# design.net
KiCad netlist of a schematic drawn in Altium Designer
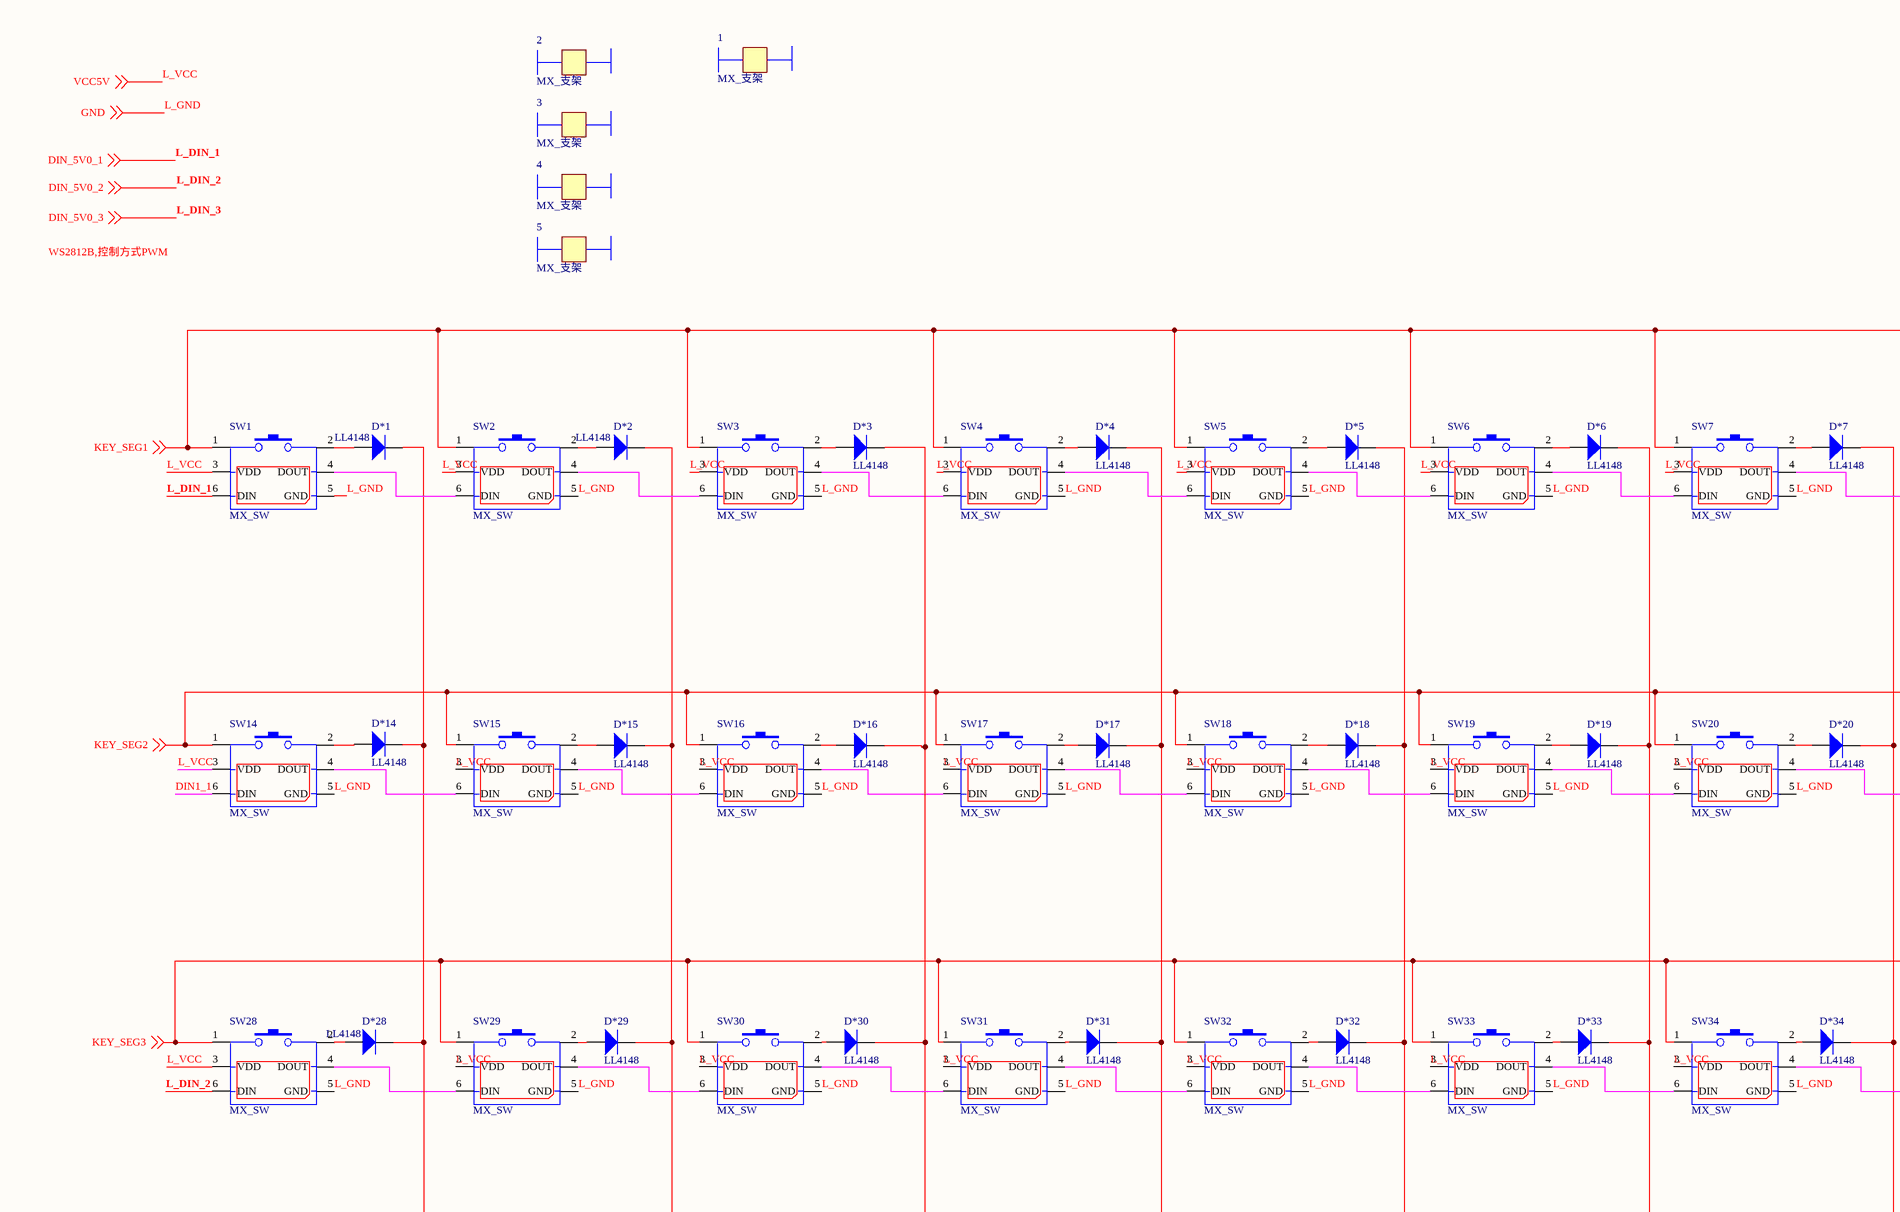
[diagram p0: 机械键盘.SchDoc, top left]
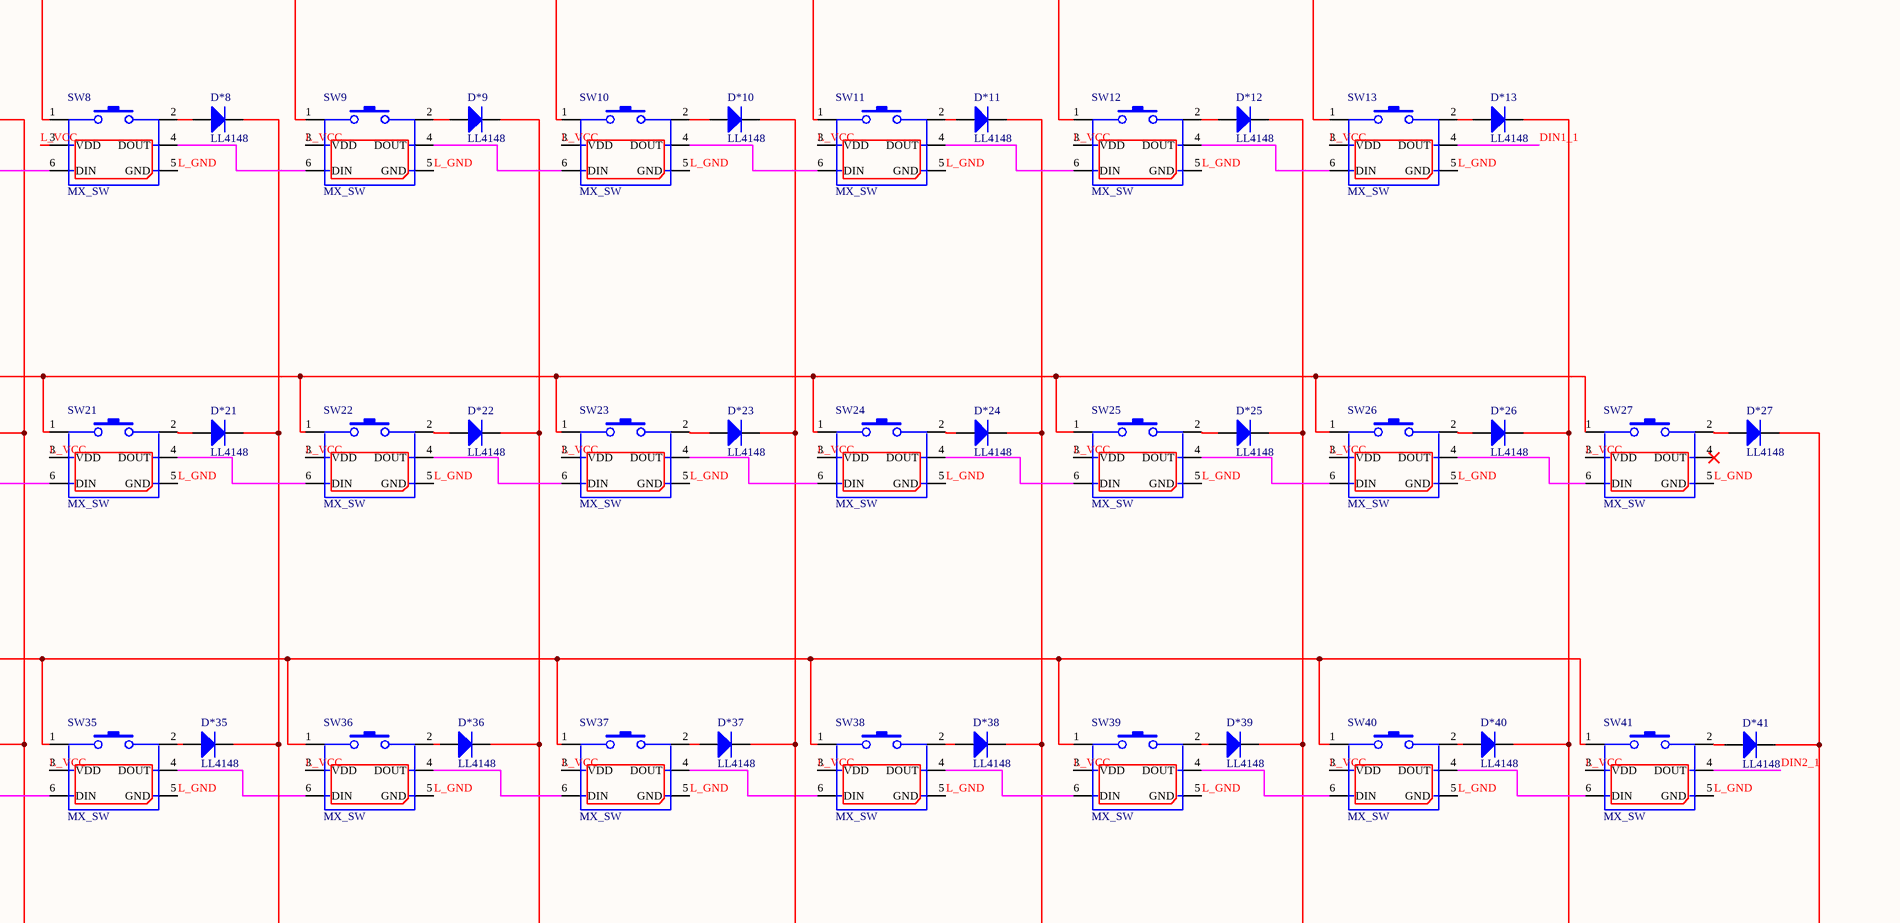
[diagram p1: 机械键盘.SchDoc, top right]
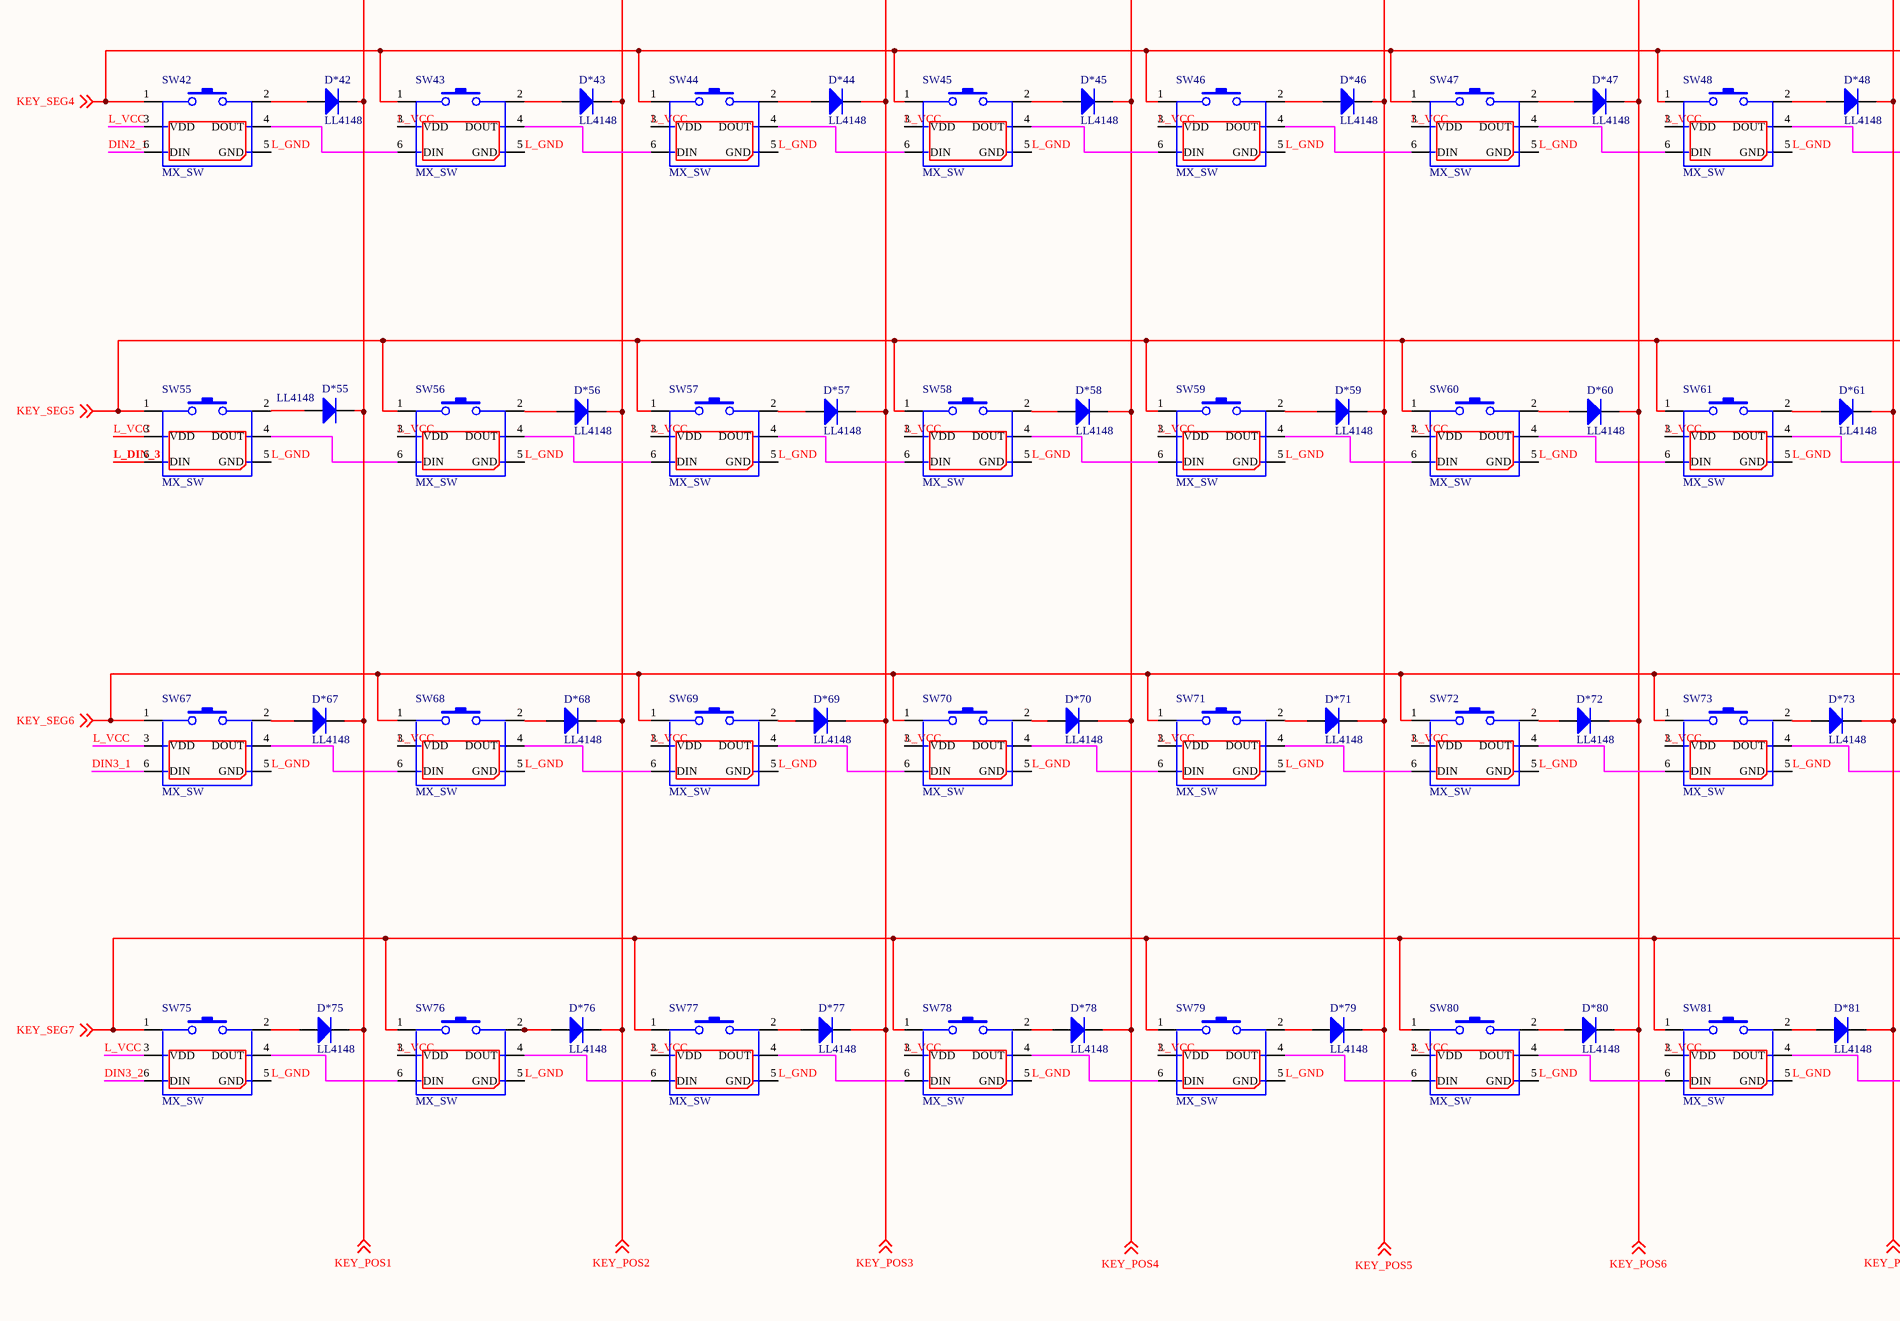
[diagram p2: 机械键盘.SchDoc, bottom left]
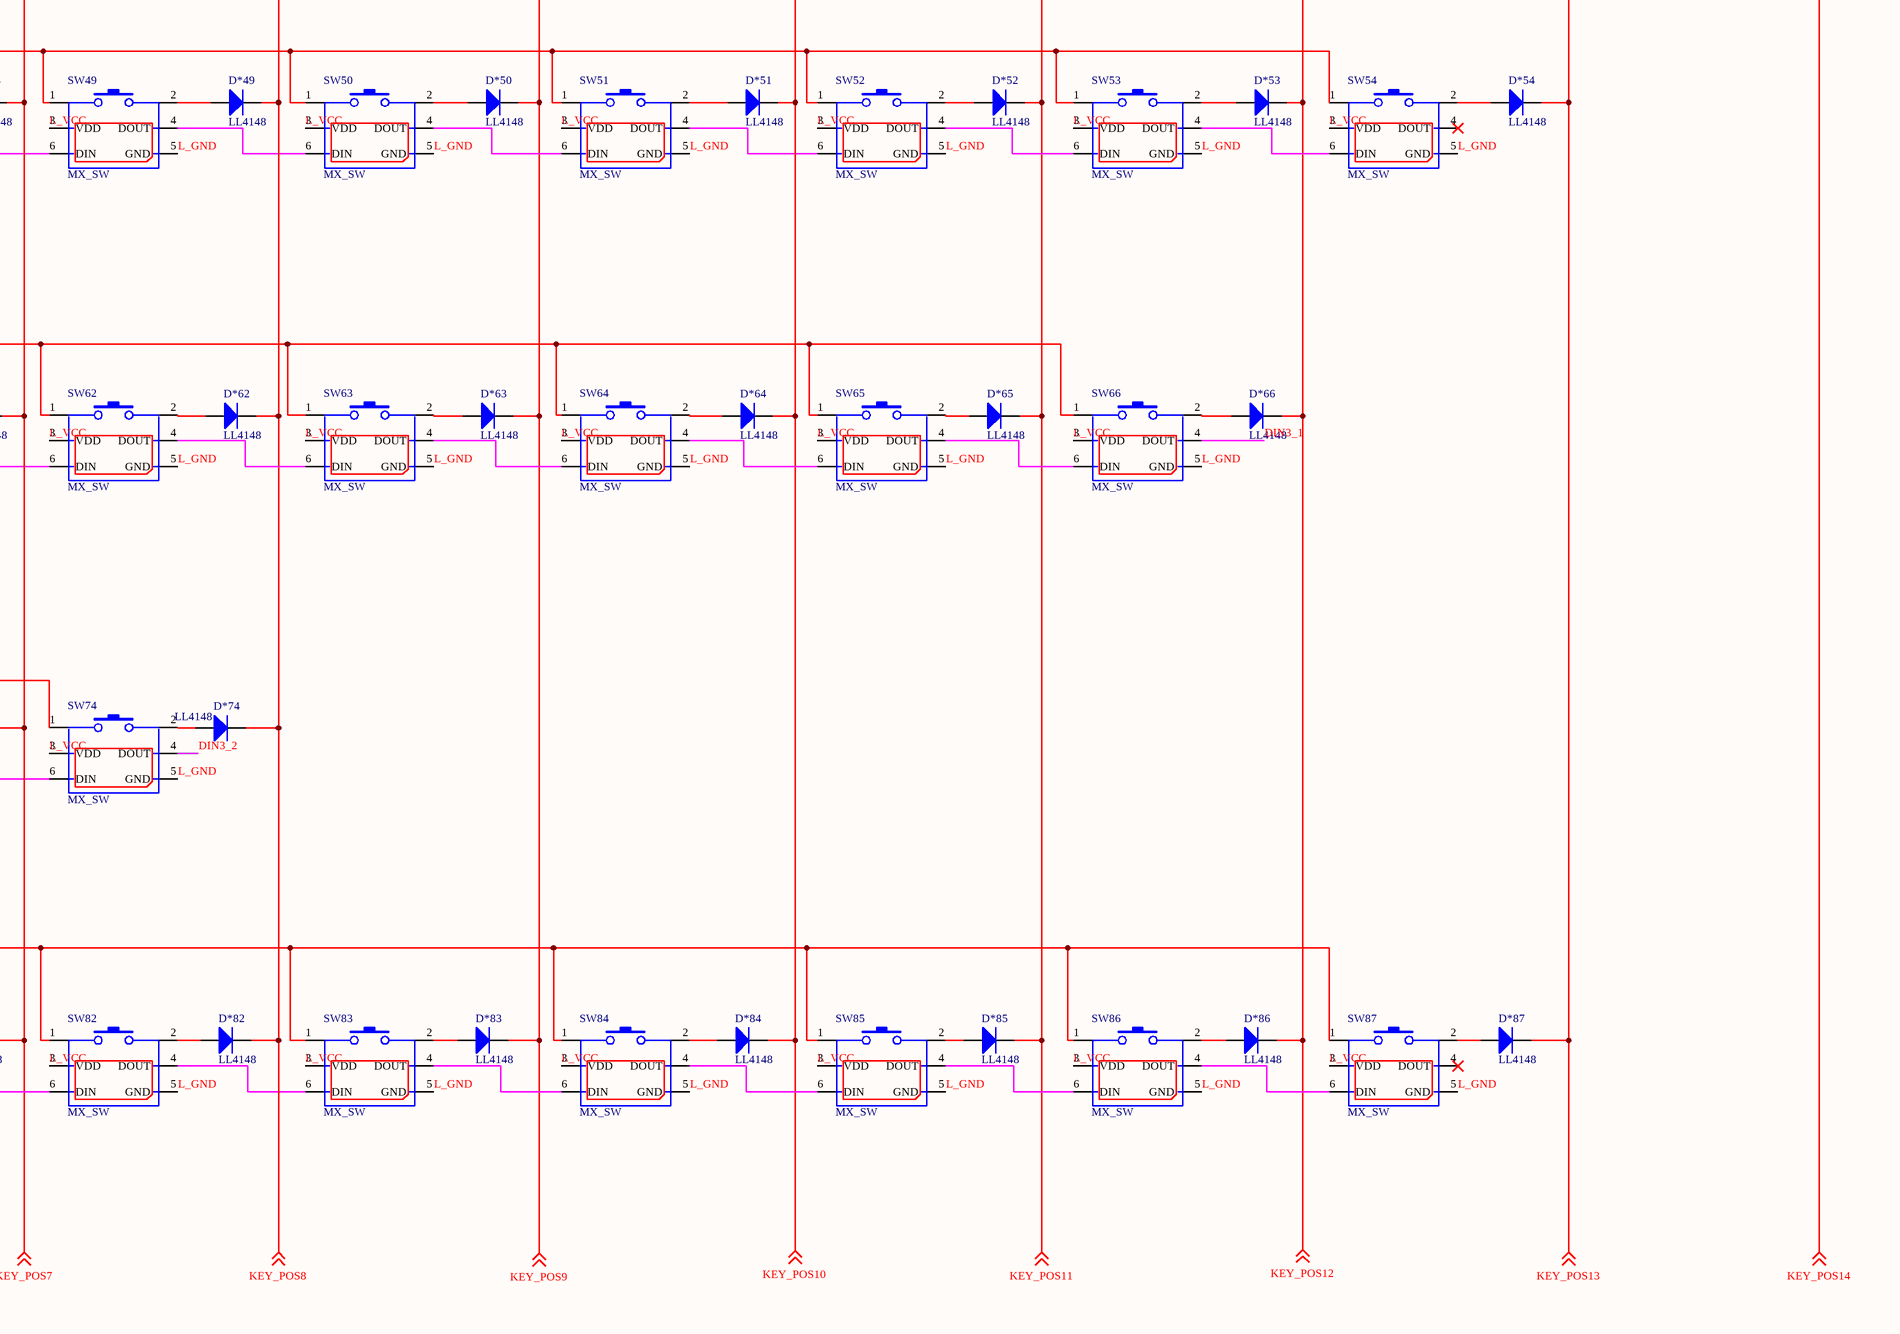
[diagram p3: 机械键盘.SchDoc, bottom right]

(export (version "E")
  (design (tool "Eeschema 10.0.6"))
  (components
    (comp (ref "1") (value "MX_支架") (footprint "机械键盘:1x6.25") (libsource (lib "机械键盘") (part "MX_支架")))
    (comp (ref "2") (value "MX_支架") (footprint "机械键盘:1x2") (libsource (lib "机械键盘") (part "MX_支架")))
    (comp (ref "3") (value "MX_支架") (footprint "机械键盘:1x2") (libsource (lib "机械键盘") (part "MX_支架")))
    (comp (ref "4") (value "MX_支架") (footprint "机械键盘:1x2") (libsource (lib "机械键盘") (part "MX_支架")))
    (comp (ref "5") (value "MX_支架") (footprint "机械键盘:1x2") (libsource (lib "机械键盘") (part "MX_支架")))
    (comp (ref "D*1")
      (value "LL4148")
      (footprint "mx_pcb_library:LL-34_L3.7-W1.6-RD")
      (libsource (lib "mx_pcb_library") (part "LL4148"))
    )
    (comp (ref "D*2")
      (value "LL4148")
      (footprint "mx_pcb_library:LL-34_L3.7-W1.6-RD")
      (libsource (lib "mx_pcb_library") (part "LL4148"))
    )
    (comp (ref "D*3")
      (value "LL4148")
      (footprint "mx_pcb_library:LL-34_L3.7-W1.6-RD")
      (libsource (lib "mx_pcb_library") (part "LL4148"))
    )
    (comp (ref "D*4")
      (value "LL4148")
      (footprint "mx_pcb_library:LL-34_L3.7-W1.6-RD")
      (libsource (lib "mx_pcb_library") (part "LL4148"))
    )
    (comp (ref "D*5")
      (value "LL4148")
      (footprint "mx_pcb_library:LL-34_L3.7-W1.6-RD")
      (libsource (lib "mx_pcb_library") (part "LL4148"))
    )
    (comp (ref "D*6")
      (value "LL4148")
      (footprint "mx_pcb_library:LL-34_L3.7-W1.6-RD")
      (libsource (lib "mx_pcb_library") (part "LL4148"))
    )
    (comp (ref "D*7")
      (value "LL4148")
      (footprint "mx_pcb_library:LL-34_L3.7-W1.6-RD")
      (libsource (lib "mx_pcb_library") (part "LL4148"))
    )
    (comp (ref "D*8")
      (value "LL4148")
      (footprint "mx_pcb_library:LL-34_L3.7-W1.6-RD")
      (libsource (lib "mx_pcb_library") (part "LL4148"))
    )
    (comp (ref "D*9")
      (value "LL4148")
      (footprint "mx_pcb_library:LL-34_L3.7-W1.6-RD")
      (libsource (lib "mx_pcb_library") (part "LL4148"))
    )
    (comp (ref "D*10")
      (value "LL4148")
      (footprint "mx_pcb_library:LL-34_L3.7-W1.6-RD")
      (libsource (lib "mx_pcb_library") (part "LL4148"))
    )
    (comp (ref "D*11")
      (value "LL4148")
      (footprint "mx_pcb_library:LL-34_L3.7-W1.6-RD")
      (libsource (lib "mx_pcb_library") (part "LL4148"))
    )
    (comp (ref "D*12")
      (value "LL4148")
      (footprint "mx_pcb_library:LL-34_L3.7-W1.6-RD")
      (libsource (lib "mx_pcb_library") (part "LL4148"))
    )
    (comp (ref "D*13")
      (value "LL4148")
      (footprint "mx_pcb_library:LL-34_L3.7-W1.6-RD")
      (libsource (lib "mx_pcb_library") (part "LL4148"))
    )
    (comp (ref "D*14")
      (value "LL4148")
      (footprint "mx_pcb_library:LL-34_L3.7-W1.6-RD")
      (libsource (lib "mx_pcb_library") (part "LL4148"))
    )
    (comp (ref "D*15")
      (value "LL4148")
      (footprint "mx_pcb_library:LL-34_L3.7-W1.6-RD")
      (libsource (lib "mx_pcb_library") (part "LL4148"))
    )
    (comp (ref "D*16")
      (value "LL4148")
      (footprint "mx_pcb_library:LL-34_L3.7-W1.6-RD")
      (libsource (lib "mx_pcb_library") (part "LL4148"))
    )
    (comp (ref "D*17")
      (value "LL4148")
      (footprint "mx_pcb_library:LL-34_L3.7-W1.6-RD")
      (libsource (lib "mx_pcb_library") (part "LL4148"))
    )
    (comp (ref "D*18")
      (value "LL4148")
      (footprint "mx_pcb_library:LL-34_L3.7-W1.6-RD")
      (libsource (lib "mx_pcb_library") (part "LL4148"))
    )
    (comp (ref "D*19")
      (value "LL4148")
      (footprint "mx_pcb_library:LL-34_L3.7-W1.6-RD")
      (libsource (lib "mx_pcb_library") (part "LL4148"))
    )
    (comp (ref "D*20")
      (value "LL4148")
      (footprint "mx_pcb_library:LL-34_L3.7-W1.6-RD")
      (libsource (lib "mx_pcb_library") (part "LL4148"))
    )
    (comp (ref "D*21")
      (value "LL4148")
      (footprint "mx_pcb_library:LL-34_L3.7-W1.6-RD")
      (libsource (lib "mx_pcb_library") (part "LL4148"))
    )
    (comp (ref "D*22")
      (value "LL4148")
      (footprint "mx_pcb_library:LL-34_L3.7-W1.6-RD")
      (libsource (lib "mx_pcb_library") (part "LL4148"))
    )
    (comp (ref "D*23")
      (value "LL4148")
      (footprint "mx_pcb_library:LL-34_L3.7-W1.6-RD")
      (libsource (lib "mx_pcb_library") (part "LL4148"))
    )
    (comp (ref "D*24")
      (value "LL4148")
      (footprint "mx_pcb_library:LL-34_L3.7-W1.6-RD")
      (libsource (lib "mx_pcb_library") (part "LL4148"))
    )
    (comp (ref "D*25")
      (value "LL4148")
      (footprint "mx_pcb_library:LL-34_L3.7-W1.6-RD")
      (libsource (lib "mx_pcb_library") (part "LL4148"))
    )
    (comp (ref "D*26")
      (value "LL4148")
      (footprint "mx_pcb_library:LL-34_L3.7-W1.6-RD")
      (libsource (lib "mx_pcb_library") (part "LL4148"))
    )
    (comp (ref "D*27")
      (value "LL4148")
      (footprint "mx_pcb_library:LL-34_L3.7-W1.6-RD")
      (libsource (lib "mx_pcb_library") (part "LL4148"))
    )
    (comp (ref "D*28")
      (value "LL4148")
      (footprint "mx_pcb_library:LL-34_L3.7-W1.6-RD")
      (libsource (lib "mx_pcb_library") (part "LL4148"))
    )
    (comp (ref "D*29")
      (value "LL4148")
      (footprint "mx_pcb_library:LL-34_L3.7-W1.6-RD")
      (libsource (lib "mx_pcb_library") (part "LL4148"))
    )
    (comp (ref "D*30")
      (value "LL4148")
      (footprint "mx_pcb_library:LL-34_L3.7-W1.6-RD")
      (libsource (lib "mx_pcb_library") (part "LL4148"))
    )
    (comp (ref "D*31")
      (value "LL4148")
      (footprint "mx_pcb_library:LL-34_L3.7-W1.6-RD")
      (libsource (lib "mx_pcb_library") (part "LL4148"))
    )
    (comp (ref "D*32")
      (value "LL4148")
      (footprint "mx_pcb_library:LL-34_L3.7-W1.6-RD")
      (libsource (lib "mx_pcb_library") (part "LL4148"))
    )
    (comp (ref "D*33")
      (value "LL4148")
      (footprint "mx_pcb_library:LL-34_L3.7-W1.6-RD")
      (libsource (lib "mx_pcb_library") (part "LL4148"))
    )
    (comp (ref "D*34")
      (value "LL4148")
      (footprint "mx_pcb_library:LL-34_L3.7-W1.6-RD")
      (libsource (lib "mx_pcb_library") (part "LL4148"))
    )
    (comp (ref "D*35")
      (value "LL4148")
      (footprint "mx_pcb_library:LL-34_L3.7-W1.6-RD")
      (libsource (lib "mx_pcb_library") (part "LL4148"))
    )
    (comp (ref "D*36")
      (value "LL4148")
      (footprint "mx_pcb_library:LL-34_L3.7-W1.6-RD")
      (libsource (lib "mx_pcb_library") (part "LL4148"))
    )
    (comp (ref "D*37")
      (value "LL4148")
      (footprint "mx_pcb_library:LL-34_L3.7-W1.6-RD")
      (libsource (lib "mx_pcb_library") (part "LL4148"))
    )
    (comp (ref "D*38")
      (value "LL4148")
      (footprint "mx_pcb_library:LL-34_L3.7-W1.6-RD")
      (libsource (lib "mx_pcb_library") (part "LL4148"))
    )
    (comp (ref "D*39")
      (value "LL4148")
      (footprint "mx_pcb_library:LL-34_L3.7-W1.6-RD")
      (libsource (lib "mx_pcb_library") (part "LL4148"))
    )
    (comp (ref "D*40")
      (value "LL4148")
      (footprint "mx_pcb_library:LL-34_L3.7-W1.6-RD")
      (libsource (lib "mx_pcb_library") (part "LL4148"))
    )
    (comp (ref "D*41")
      (value "LL4148")
      (footprint "mx_pcb_library:LL-34_L3.7-W1.6-RD")
      (libsource (lib "mx_pcb_library") (part "LL4148"))
    )
    (comp (ref "D*42")
      (value "LL4148")
      (footprint "mx_pcb_library:LL-34_L3.7-W1.6-RD")
      (libsource (lib "mx_pcb_library") (part "LL4148"))
    )
    (comp (ref "D*43")
      (value "LL4148")
      (footprint "mx_pcb_library:LL-34_L3.7-W1.6-RD")
      (libsource (lib "mx_pcb_library") (part "LL4148"))
    )
    (comp (ref "D*44")
      (value "LL4148")
      (footprint "mx_pcb_library:LL-34_L3.7-W1.6-RD")
      (libsource (lib "mx_pcb_library") (part "LL4148"))
    )
    (comp (ref "D*45")
      (value "LL4148")
      (footprint "mx_pcb_library:LL-34_L3.7-W1.6-RD")
      (libsource (lib "mx_pcb_library") (part "LL4148"))
    )
    (comp (ref "D*46")
      (value "LL4148")
      (footprint "mx_pcb_library:LL-34_L3.7-W1.6-RD")
      (libsource (lib "mx_pcb_library") (part "LL4148"))
    )
    (comp (ref "D*47")
      (value "LL4148")
      (footprint "mx_pcb_library:LL-34_L3.7-W1.6-RD")
      (libsource (lib "mx_pcb_library") (part "LL4148"))
    )
    (comp (ref "D*48")
      (value "LL4148")
      (footprint "mx_pcb_library:LL-34_L3.7-W1.6-RD")
      (libsource (lib "mx_pcb_library") (part "LL4148"))
    )
    (comp (ref "D*49")
      (value "LL4148")
      (footprint "mx_pcb_library:LL-34_L3.7-W1.6-RD")
      (libsource (lib "mx_pcb_library") (part "LL4148"))
    )
    (comp (ref "D*50")
      (value "LL4148")
      (footprint "mx_pcb_library:LL-34_L3.7-W1.6-RD")
      (libsource (lib "mx_pcb_library") (part "LL4148"))
    )
    (comp (ref "D*51")
      (value "LL4148")
      (footprint "mx_pcb_library:LL-34_L3.7-W1.6-RD")
      (libsource (lib "mx_pcb_library") (part "LL4148"))
    )
    (comp (ref "D*52")
      (value "LL4148")
      (footprint "mx_pcb_library:LL-34_L3.7-W1.6-RD")
      (libsource (lib "mx_pcb_library") (part "LL4148"))
    )
    (comp (ref "D*53")
      (value "LL4148")
      (footprint "mx_pcb_library:LL-34_L3.7-W1.6-RD")
      (libsource (lib "mx_pcb_library") (part "LL4148"))
    )
    (comp (ref "D*54")
      (value "LL4148")
      (footprint "mx_pcb_library:LL-34_L3.7-W1.6-RD")
      (libsource (lib "mx_pcb_library") (part "LL4148"))
    )
    (comp (ref "D*55")
      (value "LL4148")
      (footprint "mx_pcb_library:LL-34_L3.7-W1.6-RD")
      (libsource (lib "mx_pcb_library") (part "LL4148"))
    )
    (comp (ref "D*56")
      (value "LL4148")
      (footprint "mx_pcb_library:LL-34_L3.7-W1.6-RD")
      (libsource (lib "mx_pcb_library") (part "LL4148"))
    )
    (comp (ref "D*57")
      (value "LL4148")
      (footprint "mx_pcb_library:LL-34_L3.7-W1.6-RD")
      (libsource (lib "mx_pcb_library") (part "LL4148"))
    )
    (comp (ref "D*58")
      (value "LL4148")
      (footprint "mx_pcb_library:LL-34_L3.7-W1.6-RD")
      (libsource (lib "mx_pcb_library") (part "LL4148"))
    )
    (comp (ref "D*59")
      (value "LL4148")
      (footprint "mx_pcb_library:LL-34_L3.7-W1.6-RD")
      (libsource (lib "mx_pcb_library") (part "LL4148"))
    )
    (comp (ref "D*60")
      (value "LL4148")
      (footprint "mx_pcb_library:LL-34_L3.7-W1.6-RD")
      (libsource (lib "mx_pcb_library") (part "LL4148"))
    )
    (comp (ref "D*61")
      (value "LL4148")
      (footprint "mx_pcb_library:LL-34_L3.7-W1.6-RD")
      (libsource (lib "mx_pcb_library") (part "LL4148"))
    )
    (comp (ref "D*62")
      (value "LL4148")
      (footprint "mx_pcb_library:LL-34_L3.7-W1.6-RD")
      (libsource (lib "mx_pcb_library") (part "LL4148"))
    )
    (comp (ref "D*63")
      (value "LL4148")
      (footprint "mx_pcb_library:LL-34_L3.7-W1.6-RD")
      (libsource (lib "mx_pcb_library") (part "LL4148"))
    )
    (comp (ref "D*64")
      (value "LL4148")
      (footprint "mx_pcb_library:LL-34_L3.7-W1.6-RD")
      (libsource (lib "mx_pcb_library") (part "LL4148"))
    )
    (comp (ref "D*65")
      (value "LL4148")
      (footprint "mx_pcb_library:LL-34_L3.7-W1.6-RD")
      (libsource (lib "mx_pcb_library") (part "LL4148"))
    )
    (comp (ref "D*66")
      (value "LL4148")
      (footprint "mx_pcb_library:LL-34_L3.7-W1.6-RD")
      (libsource (lib "mx_pcb_library") (part "LL4148"))
    )
    (comp (ref "D*67")
      (value "LL4148")
      (footprint "mx_pcb_library:LL-34_L3.7-W1.6-RD")
      (libsource (lib "mx_pcb_library") (part "LL4148"))
    )
    (comp (ref "D*68")
      (value "LL4148")
      (footprint "mx_pcb_library:LL-34_L3.7-W1.6-RD")
      (libsource (lib "mx_pcb_library") (part "LL4148"))
    )
    (comp (ref "D*69")
      (value "LL4148")
      (footprint "mx_pcb_library:LL-34_L3.7-W1.6-RD")
      (libsource (lib "mx_pcb_library") (part "LL4148"))
    )
    (comp (ref "D*70")
      (value "LL4148")
      (footprint "mx_pcb_library:LL-34_L3.7-W1.6-RD")
      (libsource (lib "mx_pcb_library") (part "LL4148"))
    )
    (comp (ref "D*71")
      (value "LL4148")
      (footprint "mx_pcb_library:LL-34_L3.7-W1.6-RD")
      (libsource (lib "mx_pcb_library") (part "LL4148"))
    )
    (comp (ref "D*72")
      (value "LL4148")
      (footprint "mx_pcb_library:LL-34_L3.7-W1.6-RD")
      (libsource (lib "mx_pcb_library") (part "LL4148"))
    )
    (comp (ref "D*73")
      (value "LL4148")
      (footprint "mx_pcb_library:LL-34_L3.7-W1.6-RD")
      (libsource (lib "mx_pcb_library") (part "LL4148"))
    )
    (comp (ref "D*74")
      (value "LL4148")
      (footprint "mx_pcb_library:LL-34_L3.7-W1.6-RD")
      (libsource (lib "mx_pcb_library") (part "LL4148"))
    )
    (comp (ref "D*75")
      (value "LL4148")
      (footprint "mx_pcb_library:LL-34_L3.7-W1.6-RD")
      (libsource (lib "mx_pcb_library") (part "LL4148"))
    )
    (comp (ref "D*76")
      (value "LL4148")
      (footprint "mx_pcb_library:LL-34_L3.7-W1.6-RD")
      (libsource (lib "mx_pcb_library") (part "LL4148"))
    )
    (comp (ref "D*77")
      (value "LL4148")
      (footprint "mx_pcb_library:LL-34_L3.7-W1.6-RD")
      (libsource (lib "mx_pcb_library") (part "LL4148"))
    )
    (comp (ref "D*78")
      (value "LL4148")
      (footprint "mx_pcb_library:LL-34_L3.7-W1.6-RD")
      (libsource (lib "mx_pcb_library") (part "LL4148"))
    )
    (comp (ref "D*79")
      (value "LL4148")
      (footprint "mx_pcb_library:LL-34_L3.7-W1.6-RD")
      (libsource (lib "mx_pcb_library") (part "LL4148"))
    )
    (comp (ref "D*80")
      (value "LL4148")
      (footprint "mx_pcb_library:LL-34_L3.7-W1.6-RD")
      (libsource (lib "mx_pcb_library") (part "LL4148"))
    )
    (comp (ref "D*81")
      (value "LL4148")
      (footprint "mx_pcb_library:LL-34_L3.7-W1.6-RD")
      (libsource (lib "mx_pcb_library") (part "LL4148"))
    )
    (comp (ref "D*82")
      (value "LL4148")
      (footprint "mx_pcb_library:LL-34_L3.7-W1.6-RD")
      (libsource (lib "mx_pcb_library") (part "LL4148"))
    )
    (comp (ref "D*83")
      (value "LL4148")
      (footprint "mx_pcb_library:LL-34_L3.7-W1.6-RD")
      (libsource (lib "mx_pcb_library") (part "LL4148"))
    )
    (comp (ref "D*84")
      (value "LL4148")
      (footprint "mx_pcb_library:LL-34_L3.7-W1.6-RD")
      (libsource (lib "mx_pcb_library") (part "LL4148"))
    )
    (comp (ref "D*85")
      (value "LL4148")
      (footprint "mx_pcb_library:LL-34_L3.7-W1.6-RD")
      (libsource (lib "mx_pcb_library") (part "LL4148"))
    )
    (comp (ref "D*86")
      (value "LL4148")
      (footprint "mx_pcb_library:LL-34_L3.7-W1.6-RD")
      (libsource (lib "mx_pcb_library") (part "LL4148"))
    )
    (comp (ref "D*87")
      (value "LL4148")
      (footprint "mx_pcb_library:LL-34_L3.7-W1.6-RD")
      (libsource (lib "mx_pcb_library") (part "LL4148"))
    )
    (comp (ref "SW1")
      (value "MX_SW")
      (footprint "机械键盘:MX_SW-7")
      (description "with Fixation pins  1-Pole w/Diode")
      (libsource (lib "机械键盘") (part "MX_SW-7"))
    )
    (comp (ref "SW2")
      (value "MX_SW")
      (footprint "机械键盘:MX_SW-7")
      (description "with Fixation pins  1-Pole w/Diode")
      (libsource (lib "机械键盘") (part "MX_SW-7"))
    )
    (comp (ref "SW3")
      (value "MX_SW")
      (footprint "机械键盘:MX_SW-7")
      (description "with Fixation pins  1-Pole w/Diode")
      (libsource (lib "机械键盘") (part "MX_SW-7"))
    )
    (comp (ref "SW4")
      (value "MX_SW")
      (footprint "机械键盘:MX_SW-7")
      (description "with Fixation pins  1-Pole w/Diode")
      (libsource (lib "机械键盘") (part "MX_SW-7"))
    )
    (comp (ref "SW5")
      (value "MX_SW")
      (footprint "机械键盘:MX_SW-7")
      (description "with Fixation pins  1-Pole w/Diode")
      (libsource (lib "机械键盘") (part "MX_SW-7"))
    )
    (comp (ref "SW6")
      (value "MX_SW")
      (footprint "机械键盘:MX_SW-7")
      (description "with Fixation pins  1-Pole w/Diode")
      (libsource (lib "机械键盘") (part "MX_SW-7"))
    )
    (comp (ref "SW7")
      (value "MX_SW")
      (footprint "机械键盘:MX_SW-7")
      (description "with Fixation pins  1-Pole w/Diode")
      (libsource (lib "机械键盘") (part "MX_SW-7"))
    )
    (comp (ref "SW8")
      (value "MX_SW")
      (footprint "机械键盘:MX_SW-7")
      (description "with Fixation pins  1-Pole w/Diode")
      (libsource (lib "机械键盘") (part "MX_SW-7"))
    )
    (comp (ref "SW9")
      (value "MX_SW")
      (footprint "机械键盘:MX_SW-7")
      (description "with Fixation pins  1-Pole w/Diode")
      (libsource (lib "机械键盘") (part "MX_SW-7"))
    )
    (comp (ref "SW10")
      (value "MX_SW")
      (footprint "机械键盘:MX_SW-7")
      (description "with Fixation pins  1-Pole w/Diode")
      (libsource (lib "机械键盘") (part "MX_SW-7"))
    )
    (comp (ref "SW11")
      (value "MX_SW")
      (footprint "机械键盘:MX_SW-7")
      (description "with Fixation pins  1-Pole w/Diode")
      (libsource (lib "机械键盘") (part "MX_SW-7"))
    )
    (comp (ref "SW12")
      (value "MX_SW")
      (footprint "机械键盘:MX_SW-7")
      (description "with Fixation pins  1-Pole w/Diode")
      (libsource (lib "机械键盘") (part "MX_SW-7"))
    )
    (comp (ref "SW13")
      (value "MX_SW")
      (footprint "机械键盘:MX_SW-7")
      (description "with Fixation pins  1-Pole w/Diode")
      (libsource (lib "机械键盘") (part "MX_SW-7"))
    )
    (comp (ref "SW14")
      (value "MX_SW")
      (footprint "机械键盘:MX_SW-7")
      (description "with Fixation pins  1-Pole w/Diode")
      (libsource (lib "机械键盘") (part "MX_SW-7"))
    )
    (comp (ref "SW15")
      (value "MX_SW")
      (footprint "机械键盘:MX_SW-7")
      (description "with Fixation pins  1-Pole w/Diode")
      (libsource (lib "机械键盘") (part "MX_SW-7"))
    )
    (comp (ref "SW16")
      (value "MX_SW")
      (footprint "机械键盘:MX_SW-7")
      (description "with Fixation pins  1-Pole w/Diode")
      (libsource (lib "机械键盘") (part "MX_SW-7"))
    )
    (comp (ref "SW17")
      (value "MX_SW")
      (footprint "机械键盘:MX_SW-7")
      (description "with Fixation pins  1-Pole w/Diode")
      (libsource (lib "机械键盘") (part "MX_SW-7"))
    )
    (comp (ref "SW18")
      (value "MX_SW")
      (footprint "机械键盘:MX_SW-7")
      (description "with Fixation pins  1-Pole w/Diode")
      (libsource (lib "机械键盘") (part "MX_SW-7"))
    )
    (comp (ref "SW19")
      (value "MX_SW")
      (footprint "机械键盘:MX_SW-7")
      (description "with Fixation pins  1-Pole w/Diode")
      (libsource (lib "机械键盘") (part "MX_SW-7"))
    )
    (comp (ref "SW20")
      (value "MX_SW")
      (footprint "机械键盘:MX_SW-7")
      (description "with Fixation pins  1-Pole w/Diode")
      (libsource (lib "机械键盘") (part "MX_SW-7"))
    )
    (comp (ref "SW21")
      (value "MX_SW")
      (footprint "机械键盘:MX_SW-7")
      (description "with Fixation pins  1-Pole w/Diode")
      (libsource (lib "机械键盘") (part "MX_SW-7"))
    )
    (comp (ref "SW22")
      (value "MX_SW")
      (footprint "机械键盘:MX_SW-7")
      (description "with Fixation pins  1-Pole w/Diode")
      (libsource (lib "机械键盘") (part "MX_SW-7"))
    )
    (comp (ref "SW23")
      (value "MX_SW")
      (footprint "机械键盘:MX_SW-7")
      (description "with Fixation pins  1-Pole w/Diode")
      (libsource (lib "机械键盘") (part "MX_SW-7"))
    )
    (comp (ref "SW24")
      (value "MX_SW")
      (footprint "机械键盘:MX_SW-7")
      (description "with Fixation pins  1-Pole w/Diode")
      (libsource (lib "机械键盘") (part "MX_SW-7"))
    )
    (comp (ref "SW25")
      (value "MX_SW")
      (footprint "机械键盘:MX_SW-7")
      (description "with Fixation pins  1-Pole w/Diode")
      (libsource (lib "机械键盘") (part "MX_SW-7"))
    )
    (comp (ref "SW26")
      (value "MX_SW")
      (footprint "机械键盘:MX_SW-7")
      (description "with Fixation pins  1-Pole w/Diode")
      (libsource (lib "机械键盘") (part "MX_SW-7"))
    )
    (comp (ref "SW27")
      (value "MX_SW")
      (footprint "机械键盘:MX_Backspace")
      (description "with Fixation pins  1-Pole w/Diode")
      (libsource (lib "机械键盘") (part "MX_SW-7"))
    )
    (comp (ref "SW28")
      (value "MX_SW")
      (footprint "MX_Tab")
      (description "with Fixation pins  1-Pole w/Diode")
      (libsource (lib "机械键盘") (part "MX_SW-7"))
    )
    (comp (ref "SW29")
      (value "MX_SW")
      (footprint "机械键盘:MX_SW-7")
      (description "with Fixation pins  1-Pole w/Diode")
      (libsource (lib "机械键盘") (part "MX_SW-7"))
    )
    (comp (ref "SW30")
      (value "MX_SW")
      (footprint "机械键盘:MX_SW-7")
      (description "with Fixation pins  1-Pole w/Diode")
      (libsource (lib "机械键盘") (part "MX_SW-7"))
    )
    (comp (ref "SW31")
      (value "MX_SW")
      (footprint "机械键盘:MX_SW-7")
      (description "with Fixation pins  1-Pole w/Diode")
      (libsource (lib "机械键盘") (part "MX_SW-7"))
    )
    (comp (ref "SW32")
      (value "MX_SW")
      (footprint "机械键盘:MX_SW-7")
      (description "with Fixation pins  1-Pole w/Diode")
      (libsource (lib "机械键盘") (part "MX_SW-7"))
    )
    (comp (ref "SW33")
      (value "MX_SW")
      (footprint "机械键盘:MX_SW-7")
      (description "with Fixation pins  1-Pole w/Diode")
      (libsource (lib "机械键盘") (part "MX_SW-7"))
    )
    (comp (ref "SW34")
      (value "MX_SW")
      (footprint "机械键盘:MX_SW-7")
      (description "with Fixation pins  1-Pole w/Diode")
      (libsource (lib "机械键盘") (part "MX_SW-7"))
    )
    (comp (ref "SW35")
      (value "MX_SW")
      (footprint "机械键盘:MX_SW-7")
      (description "with Fixation pins  1-Pole w/Diode")
      (libsource (lib "机械键盘") (part "MX_SW-7"))
    )
    (comp (ref "SW36")
      (value "MX_SW")
      (footprint "机械键盘:MX_SW-7")
      (description "with Fixation pins  1-Pole w/Diode")
      (libsource (lib "机械键盘") (part "MX_SW-7"))
    )
    (comp (ref "SW37")
      (value "MX_SW")
      (footprint "机械键盘:MX_SW-7")
      (description "with Fixation pins  1-Pole w/Diode")
      (libsource (lib "机械键盘") (part "MX_SW-7"))
    )
    (comp (ref "SW38")
      (value "MX_SW")
      (footprint "机械键盘:MX_SW-7")
      (description "with Fixation pins  1-Pole w/Diode")
      (libsource (lib "机械键盘") (part "MX_SW-7"))
    )
    (comp (ref "SW39")
      (value "MX_SW")
      (footprint "机械键盘:MX_SW-7")
      (description "with Fixation pins  1-Pole w/Diode")
      (libsource (lib "机械键盘") (part "MX_SW-7"))
    )
    (comp (ref "SW40")
      (value "MX_SW")
      (footprint "机械键盘:MX_SW-7")
      (description "with Fixation pins  1-Pole w/Diode")
      (libsource (lib "机械键盘") (part "MX_SW-7"))
    )
    (comp (ref "SW41")
      (value "MX_SW")
      (footprint "机械键盘:MX_Tab")
      (description "with Fixation pins  1-Pole w/Diode")
      (libsource (lib "机械键盘") (part "MX_SW-7"))
    )
    (comp (ref "SW42")
      (value "MX_SW")
      (footprint "MX_CapsLock")
      (description "with Fixation pins  1-Pole w/Diode")
      (libsource (lib "机械键盘") (part "MX_SW-7"))
    )
    (comp (ref "SW43")
      (value "MX_SW")
      (footprint "机械键盘:MX_SW-7")
      (description "with Fixation pins  1-Pole w/Diode")
      (libsource (lib "机械键盘") (part "MX_SW-7"))
    )
    (comp (ref "SW44")
      (value "MX_SW")
      (footprint "机械键盘:MX_SW-7")
      (description "with Fixation pins  1-Pole w/Diode")
      (libsource (lib "机械键盘") (part "MX_SW-7"))
    )
    (comp (ref "SW45")
      (value "MX_SW")
      (footprint "机械键盘:MX_SW-7")
      (description "with Fixation pins  1-Pole w/Diode")
      (libsource (lib "机械键盘") (part "MX_SW-7"))
    )
    (comp (ref "SW46")
      (value "MX_SW")
      (footprint "机械键盘:MX_SW-7")
      (description "with Fixation pins  1-Pole w/Diode")
      (libsource (lib "机械键盘") (part "MX_SW-7"))
    )
    (comp (ref "SW47")
      (value "MX_SW")
      (footprint "机械键盘:MX_SW-7")
      (description "with Fixation pins  1-Pole w/Diode")
      (libsource (lib "机械键盘") (part "MX_SW-7"))
    )
    (comp (ref "SW48")
      (value "MX_SW")
      (footprint "机械键盘:MX_SW-7")
      (description "with Fixation pins  1-Pole w/Diode")
      (libsource (lib "机械键盘") (part "MX_SW-7"))
    )
    (comp (ref "SW49")
      (value "MX_SW")
      (footprint "机械键盘:MX_SW-7")
      (description "with Fixation pins  1-Pole w/Diode")
      (libsource (lib "机械键盘") (part "MX_SW-7"))
    )
    (comp (ref "SW50")
      (value "MX_SW")
      (footprint "机械键盘:MX_SW-7")
      (description "with Fixation pins  1-Pole w/Diode")
      (libsource (lib "机械键盘") (part "MX_SW-7"))
    )
    (comp (ref "SW51")
      (value "MX_SW")
      (footprint "机械键盘:MX_SW-7")
      (description "with Fixation pins  1-Pole w/Diode")
      (libsource (lib "机械键盘") (part "MX_SW-7"))
    )
    (comp (ref "SW52")
      (value "MX_SW")
      (footprint "机械键盘:MX_SW-7")
      (description "with Fixation pins  1-Pole w/Diode")
      (libsource (lib "机械键盘") (part "MX_SW-7"))
    )
    (comp (ref "SW53")
      (value "MX_SW")
      (footprint "机械键盘:MX_SW-7")
      (description "with Fixation pins  1-Pole w/Diode")
      (libsource (lib "机械键盘") (part "MX_SW-7"))
    )
    (comp (ref "SW54")
      (value "MX_SW")
      (footprint "机械键盘:MX_左Shift(Enter)")
      (description "with Fixation pins  1-Pole w/Diode")
      (libsource (lib "机械键盘") (part "MX_SW-7"))
    )
    (comp (ref "SW55")
      (value "MX_SW")
      (footprint "机械键盘:MX_左Shift(Enter)")
      (description "with Fixation pins  1-Pole w/Diode")
      (libsource (lib "机械键盘") (part "MX_SW-7"))
    )
    (comp (ref "SW56")
      (value "MX_SW")
      (footprint "机械键盘:MX_SW-7")
      (description "with Fixation pins  1-Pole w/Diode")
      (libsource (lib "机械键盘") (part "MX_SW-7"))
    )
    (comp (ref "SW57")
      (value "MX_SW")
      (footprint "机械键盘:MX_SW-7")
      (description "with Fixation pins  1-Pole w/Diode")
      (libsource (lib "机械键盘") (part "MX_SW-7"))
    )
    (comp (ref "SW58")
      (value "MX_SW")
      (footprint "机械键盘:MX_SW-7")
      (description "with Fixation pins  1-Pole w/Diode")
      (libsource (lib "机械键盘") (part "MX_SW-7"))
    )
    (comp (ref "SW59")
      (value "MX_SW")
      (footprint "机械键盘:MX_SW-7")
      (description "with Fixation pins  1-Pole w/Diode")
      (libsource (lib "机械键盘") (part "MX_SW-7"))
    )
    (comp (ref "SW60")
      (value "MX_SW")
      (footprint "机械键盘:MX_SW-7")
      (description "with Fixation pins  1-Pole w/Diode")
      (libsource (lib "机械键盘") (part "MX_SW-7"))
    )
    (comp (ref "SW61")
      (value "MX_SW")
      (footprint "机械键盘:MX_SW-7")
      (description "with Fixation pins  1-Pole w/Diode")
      (libsource (lib "机械键盘") (part "MX_SW-7"))
    )
    (comp (ref "SW62")
      (value "MX_SW")
      (footprint "机械键盘:MX_SW-7")
      (description "with Fixation pins  1-Pole w/Diode")
      (libsource (lib "机械键盘") (part "MX_SW-7"))
    )
    (comp (ref "SW63")
      (value "MX_SW")
      (footprint "机械键盘:MX_SW-7")
      (description "with Fixation pins  1-Pole w/Diode")
      (libsource (lib "机械键盘") (part "MX_SW-7"))
    )
    (comp (ref "SW64")
      (value "MX_SW")
      (footprint "机械键盘:MX_SW-7")
      (description "with Fixation pins  1-Pole w/Diode")
      (libsource (lib "机械键盘") (part "MX_SW-7"))
    )
    (comp (ref "SW65")
      (value "MX_SW")
      (footprint "机械键盘:MX_SW-7")
      (description "with Fixation pins  1-Pole w/Diode")
      (libsource (lib "机械键盘") (part "MX_SW-7"))
    )
    (comp (ref "SW66")
      (value "MX_SW")
      (footprint "机械键盘:MX_右Shift")
      (description "with Fixation pins  1-Pole w/Diode")
      (libsource (lib "机械键盘") (part "MX_SW-7"))
    )
    (comp (ref "SW67")
      (value "MX_SW")
      (footprint "机械键盘:MX_Ctrl(Win)(Alt)")
      (description "with Fixation pins  1-Pole w/Diode")
      (libsource (lib "机械键盘") (part "MX_SW-7"))
    )
    (comp (ref "SW68")
      (value "MX_SW")
      (footprint "MX_Ctrl(Win)(Alt)")
      (description "with Fixation pins  1-Pole w/Diode")
      (libsource (lib "机械键盘") (part "MX_SW-7"))
    )
    (comp (ref "SW69")
      (value "MX_SW")
      (footprint "MX_Ctrl(Win)(Alt)")
      (description "with Fixation pins  1-Pole w/Diode")
      (libsource (lib "机械键盘") (part "MX_SW-7"))
    )
    (comp (ref "SW70")
      (value "MX_SW")
      (footprint "机械键盘:MX_空格")
      (description "with Fixation pins  1-Pole w/Diode")
      (libsource (lib "机械键盘") (part "MX_SW-7"))
    )
    (comp (ref "SW71")
      (value "MX_SW")
      (footprint "MX_Ctrl(Win)(Alt)")
      (description "with Fixation pins  1-Pole w/Diode")
      (libsource (lib "机械键盘") (part "MX_SW-7"))
    )
    (comp (ref "SW72")
      (value "MX_SW")
      (footprint "MX_Ctrl(Win)(Alt)")
      (description "with Fixation pins  1-Pole w/Diode")
      (libsource (lib "机械键盘") (part "MX_SW-7"))
    )
    (comp (ref "SW73")
      (value "MX_SW")
      (footprint "MX_Ctrl(Win)(Alt)")
      (description "with Fixation pins  1-Pole w/Diode")
      (libsource (lib "机械键盘") (part "MX_SW-7"))
    )
    (comp (ref "SW74")
      (value "MX_SW")
      (footprint "MX_Ctrl(Win)(Alt)")
      (description "with Fixation pins  1-Pole w/Diode")
      (libsource (lib "机械键盘") (part "MX_SW-7"))
    )
    (comp (ref "SW75")
      (value "MX_SW")
      (footprint "机械键盘:MX_SW-7")
      (description "with Fixation pins  1-Pole w/Diode")
      (libsource (lib "机械键盘") (part "MX_SW-7"))
    )
    (comp (ref "SW76")
      (value "MX_SW")
      (footprint "机械键盘:MX_SW-7")
      (description "with Fixation pins  1-Pole w/Diode")
      (libsource (lib "机械键盘") (part "MX_SW-7"))
    )
    (comp (ref "SW77")
      (value "MX_SW")
      (footprint "机械键盘:MX_SW-7")
      (description "with Fixation pins  1-Pole w/Diode")
      (libsource (lib "机械键盘") (part "MX_SW-7"))
    )
    (comp (ref "SW78")
      (value "MX_SW")
      (footprint "机械键盘:MX_SW-7")
      (description "with Fixation pins  1-Pole w/Diode")
      (libsource (lib "机械键盘") (part "MX_SW-7"))
    )
    (comp (ref "SW79")
      (value "MX_SW")
      (footprint "机械键盘:MX_SW-7")
      (description "with Fixation pins  1-Pole w/Diode")
      (libsource (lib "机械键盘") (part "MX_SW-7"))
    )
    (comp (ref "SW80")
      (value "MX_SW")
      (footprint "机械键盘:MX_SW-7")
      (description "with Fixation pins  1-Pole w/Diode")
      (libsource (lib "机械键盘") (part "MX_SW-7"))
    )
    (comp (ref "SW81")
      (value "MX_SW")
      (footprint "机械键盘:MX_SW-7")
      (description "with Fixation pins  1-Pole w/Diode")
      (libsource (lib "机械键盘") (part "MX_SW-7"))
    )
    (comp (ref "SW82")
      (value "MX_SW")
      (footprint "机械键盘:MX_SW-7")
      (description "with Fixation pins  1-Pole w/Diode")
      (libsource (lib "机械键盘") (part "MX_SW-7"))
    )
    (comp (ref "SW83")
      (value "MX_SW")
      (footprint "机械键盘:MX_SW-7")
      (description "with Fixation pins  1-Pole w/Diode")
      (libsource (lib "机械键盘") (part "MX_SW-7"))
    )
    (comp (ref "SW84")
      (value "MX_SW")
      (footprint "机械键盘:MX_SW-7")
      (description "with Fixation pins  1-Pole w/Diode")
      (libsource (lib "机械键盘") (part "MX_SW-7"))
    )
    (comp (ref "SW85")
      (value "MX_SW")
      (footprint "机械键盘:MX_SW-7")
      (description "with Fixation pins  1-Pole w/Diode")
      (libsource (lib "机械键盘") (part "MX_SW-7"))
    )
    (comp (ref "SW86")
      (value "MX_SW")
      (footprint "机械键盘:MX_SW-7")
      (description "with Fixation pins  1-Pole w/Diode")
      (libsource (lib "机械键盘") (part "MX_SW-7"))
    )
    (comp (ref "SW87")
      (value "MX_SW")
      (footprint "机械键盘:MX_SW-7")
      (description "with Fixation pins  1-Pole w/Diode")
      (libsource (lib "机械键盘") (part "MX_SW-7"))
    )
  )
  (nets
    (net (code "1") (name "/DIN1_1") (class "Default")
      (node (ref "SW13") (pin "4") (pinfunction "DOUT_4") (pintype "passive"))
      (node (ref "SW14") (pin "6") (pinfunction "DIN_6") (pintype "passive"))
    )
    (net (code "2") (name "/DIN2_1") (class "Default")
      (node (ref "SW41") (pin "4") (pinfunction "DOUT_4") (pintype "passive"))
      (node (ref "SW42") (pin "6") (pinfunction "DIN_6") (pintype "passive"))
    )
    (net (code "3") (name "/DIN3_1") (class "Default")
      (node (ref "SW66") (pin "4") (pinfunction "DOUT_4") (pintype "passive"))
      (node (ref "SW67") (pin "6") (pinfunction "DIN_6") (pintype "passive"))
    )
    (net (code "4") (name "/DIN3_2") (class "Default")
      (node (ref "SW74") (pin "4") (pinfunction "DOUT_4") (pintype "passive"))
      (node (ref "SW75") (pin "6") (pinfunction "DIN_6") (pintype "passive"))
    )
    (net (code "5") (name "DIN_5V0_1") (class "Default")
      (node (ref "SW1") (pin "6") (pinfunction "DIN_6") (pintype "passive"))
    )
    (net (code "6") (name "DIN_5V0_2") (class "Default")
      (node (ref "SW28") (pin "6") (pinfunction "DIN_6") (pintype "passive"))
    )
    (net (code "7") (name "DIN_5V0_3") (class "Default")
      (node (ref "SW55") (pin "6") (pinfunction "DIN_6") (pintype "passive"))
    )
    (net (code "8") (name "GND") (class "Default")
      (node (ref "SW1") (pin "5") (pinfunction "GND_5") (pintype "passive"))
      (node (ref "SW10") (pin "5") (pinfunction "GND_5") (pintype "passive"))
      (node (ref "SW11") (pin "5") (pinfunction "GND_5") (pintype "passive"))
      (node (ref "SW12") (pin "5") (pinfunction "GND_5") (pintype "passive"))
      (node (ref "SW13") (pin "5") (pinfunction "GND_5") (pintype "passive"))
      (node (ref "SW14") (pin "5") (pinfunction "GND_5") (pintype "passive"))
      (node (ref "SW15") (pin "5") (pinfunction "GND_5") (pintype "passive"))
      (node (ref "SW16") (pin "5") (pinfunction "GND_5") (pintype "passive"))
      (node (ref "SW17") (pin "5") (pinfunction "GND_5") (pintype "passive"))
      (node (ref "SW18") (pin "5") (pinfunction "GND_5") (pintype "passive"))
      (node (ref "SW19") (pin "5") (pinfunction "GND_5") (pintype "passive"))
      (node (ref "SW2") (pin "5") (pinfunction "GND_5") (pintype "passive"))
      (node (ref "SW20") (pin "5") (pinfunction "GND_5") (pintype "passive"))
      (node (ref "SW21") (pin "5") (pinfunction "GND_5") (pintype "passive"))
      (node (ref "SW22") (pin "5") (pinfunction "GND_5") (pintype "passive"))
      (node (ref "SW23") (pin "5") (pinfunction "GND_5") (pintype "passive"))
      (node (ref "SW24") (pin "5") (pinfunction "GND_5") (pintype "passive"))
      (node (ref "SW25") (pin "5") (pinfunction "GND_5") (pintype "passive"))
      (node (ref "SW26") (pin "5") (pinfunction "GND_5") (pintype "passive"))
      (node (ref "SW27") (pin "5") (pinfunction "GND_5") (pintype "passive"))
      (node (ref "SW28") (pin "5") (pinfunction "GND_5") (pintype "passive"))
      (node (ref "SW29") (pin "5") (pinfunction "GND_5") (pintype "passive"))
      (node (ref "SW3") (pin "5") (pinfunction "GND_5") (pintype "passive"))
      (node (ref "SW30") (pin "5") (pinfunction "GND_5") (pintype "passive"))
      (node (ref "SW31") (pin "5") (pinfunction "GND_5") (pintype "passive"))
      (node (ref "SW32") (pin "5") (pinfunction "GND_5") (pintype "passive"))
      (node (ref "SW33") (pin "5") (pinfunction "GND_5") (pintype "passive"))
      (node (ref "SW34") (pin "5") (pinfunction "GND_5") (pintype "passive"))
      (node (ref "SW35") (pin "5") (pinfunction "GND_5") (pintype "passive"))
      (node (ref "SW36") (pin "5") (pinfunction "GND_5") (pintype "passive"))
      (node (ref "SW37") (pin "5") (pinfunction "GND_5") (pintype "passive"))
      (node (ref "SW38") (pin "5") (pinfunction "GND_5") (pintype "passive"))
      (node (ref "SW39") (pin "5") (pinfunction "GND_5") (pintype "passive"))
      (node (ref "SW4") (pin "5") (pinfunction "GND_5") (pintype "passive"))
      (node (ref "SW40") (pin "5") (pinfunction "GND_5") (pintype "passive"))
      (node (ref "SW41") (pin "5") (pinfunction "GND_5") (pintype "passive"))
      (node (ref "SW42") (pin "5") (pinfunction "GND_5") (pintype "passive"))
      (node (ref "SW43") (pin "5") (pinfunction "GND_5") (pintype "passive"))
      (node (ref "SW44") (pin "5") (pinfunction "GND_5") (pintype "passive"))
      (node (ref "SW45") (pin "5") (pinfunction "GND_5") (pintype "passive"))
      (node (ref "SW46") (pin "5") (pinfunction "GND_5") (pintype "passive"))
      (node (ref "SW47") (pin "5") (pinfunction "GND_5") (pintype "passive"))
      (node (ref "SW48") (pin "5") (pinfunction "GND_5") (pintype "passive"))
      (node (ref "SW49") (pin "5") (pinfunction "GND_5") (pintype "passive"))
      (node (ref "SW5") (pin "5") (pinfunction "GND_5") (pintype "passive"))
      (node (ref "SW50") (pin "5") (pinfunction "GND_5") (pintype "passive"))
      (node (ref "SW51") (pin "5") (pinfunction "GND_5") (pintype "passive"))
      (node (ref "SW52") (pin "5") (pinfunction "GND_5") (pintype "passive"))
      (node (ref "SW53") (pin "5") (pinfunction "GND_5") (pintype "passive"))
      (node (ref "SW54") (pin "5") (pinfunction "GND_5") (pintype "passive"))
      (node (ref "SW55") (pin "5") (pinfunction "GND_5") (pintype "passive"))
      (node (ref "SW56") (pin "5") (pinfunction "GND_5") (pintype "passive"))
      (node (ref "SW57") (pin "5") (pinfunction "GND_5") (pintype "passive"))
      (node (ref "SW58") (pin "5") (pinfunction "GND_5") (pintype "passive"))
      (node (ref "SW59") (pin "5") (pinfunction "GND_5") (pintype "passive"))
      (node (ref "SW6") (pin "5") (pinfunction "GND_5") (pintype "passive"))
      (node (ref "SW60") (pin "5") (pinfunction "GND_5") (pintype "passive"))
      (node (ref "SW61") (pin "5") (pinfunction "GND_5") (pintype "passive"))
      (node (ref "SW62") (pin "5") (pinfunction "GND_5") (pintype "passive"))
      (node (ref "SW63") (pin "5") (pinfunction "GND_5") (pintype "passive"))
      (node (ref "SW64") (pin "5") (pinfunction "GND_5") (pintype "passive"))
      (node (ref "SW65") (pin "5") (pinfunction "GND_5") (pintype "passive"))
      (node (ref "SW66") (pin "5") (pinfunction "GND_5") (pintype "passive"))
      (node (ref "SW67") (pin "5") (pinfunction "GND_5") (pintype "passive"))
      (node (ref "SW68") (pin "5") (pinfunction "GND_5") (pintype "passive"))
      (node (ref "SW69") (pin "5") (pinfunction "GND_5") (pintype "passive"))
      (node (ref "SW7") (pin "5") (pinfunction "GND_5") (pintype "passive"))
      (node (ref "SW70") (pin "5") (pinfunction "GND_5") (pintype "passive"))
      (node (ref "SW71") (pin "5") (pinfunction "GND_5") (pintype "passive"))
      (node (ref "SW72") (pin "5") (pinfunction "GND_5") (pintype "passive"))
      (node (ref "SW73") (pin "5") (pinfunction "GND_5") (pintype "passive"))
      (node (ref "SW74") (pin "5") (pinfunction "GND_5") (pintype "passive"))
      (node (ref "SW75") (pin "5") (pinfunction "GND_5") (pintype "passive"))
      (node (ref "SW76") (pin "5") (pinfunction "GND_5") (pintype "passive"))
      (node (ref "SW77") (pin "5") (pinfunction "GND_5") (pintype "passive"))
      (node (ref "SW78") (pin "5") (pinfunction "GND_5") (pintype "passive"))
      (node (ref "SW79") (pin "5") (pinfunction "GND_5") (pintype "passive"))
      (node (ref "SW8") (pin "5") (pinfunction "GND_5") (pintype "passive"))
      (node (ref "SW80") (pin "5") (pinfunction "GND_5") (pintype "passive"))
      (node (ref "SW81") (pin "5") (pinfunction "GND_5") (pintype "passive"))
      (node (ref "SW82") (pin "5") (pinfunction "GND_5") (pintype "passive"))
      (node (ref "SW83") (pin "5") (pinfunction "GND_5") (pintype "passive"))
      (node (ref "SW84") (pin "5") (pinfunction "GND_5") (pintype "passive"))
      (node (ref "SW85") (pin "5") (pinfunction "GND_5") (pintype "passive"))
      (node (ref "SW86") (pin "5") (pinfunction "GND_5") (pintype "passive"))
      (node (ref "SW87") (pin "5") (pinfunction "GND_5") (pintype "passive"))
      (node (ref "SW9") (pin "5") (pinfunction "GND_5") (pintype "passive"))
    )
    (net (code "9") (name "KEY_POS1") (class "Default")
      (node (ref "D*1") (pin "2") (pinfunction "2_2") (pintype "passive"))
      (node (ref "D*14") (pin "2") (pinfunction "2_2") (pintype "passive"))
      (node (ref "D*28") (pin "2") (pinfunction "2_2") (pintype "passive"))
      (node (ref "D*42") (pin "2") (pinfunction "2_2") (pintype "passive"))
      (node (ref "D*55") (pin "2") (pinfunction "2_2") (pintype "passive"))
      (node (ref "D*67") (pin "2") (pinfunction "2_2") (pintype "passive"))
      (node (ref "D*75") (pin "2") (pinfunction "2_2") (pintype "passive"))
    )
    (net (code "10") (name "KEY_POS2") (class "Default")
      (node (ref "D*15") (pin "2") (pinfunction "2_2") (pintype "passive"))
      (node (ref "D*2") (pin "2") (pinfunction "2_2") (pintype "passive"))
      (node (ref "D*29") (pin "2") (pinfunction "2_2") (pintype "passive"))
      (node (ref "D*43") (pin "2") (pinfunction "2_2") (pintype "passive"))
      (node (ref "D*56") (pin "2") (pinfunction "2_2") (pintype "passive"))
      (node (ref "D*68") (pin "2") (pinfunction "2_2") (pintype "passive"))
      (node (ref "D*76") (pin "2") (pinfunction "2_2") (pintype "passive"))
    )
    (net (code "11") (name "KEY_POS3") (class "Default")
      (node (ref "D*16") (pin "2") (pinfunction "2_2") (pintype "passive"))
      (node (ref "D*3") (pin "2") (pinfunction "2_2") (pintype "passive"))
      (node (ref "D*30") (pin "2") (pinfunction "2_2") (pintype "passive"))
      (node (ref "D*44") (pin "2") (pinfunction "2_2") (pintype "passive"))
      (node (ref "D*57") (pin "2") (pinfunction "2_2") (pintype "passive"))
      (node (ref "D*69") (pin "2") (pinfunction "2_2") (pintype "passive"))
      (node (ref "D*77") (pin "2") (pinfunction "2_2") (pintype "passive"))
    )
    (net (code "12") (name "KEY_POS4") (class "Default")
      (node (ref "D*17") (pin "2") (pinfunction "2_2") (pintype "passive"))
      (node (ref "D*31") (pin "2") (pinfunction "2_2") (pintype "passive"))
      (node (ref "D*4") (pin "2") (pinfunction "2_2") (pintype "passive"))
      (node (ref "D*45") (pin "2") (pinfunction "2_2") (pintype "passive"))
      (node (ref "D*58") (pin "2") (pinfunction "2_2") (pintype "passive"))
      (node (ref "D*70") (pin "2") (pinfunction "2_2") (pintype "passive"))
      (node (ref "D*78") (pin "2") (pinfunction "2_2") (pintype "passive"))
    )
    (net (code "13") (name "KEY_POS5") (class "Default")
      (node (ref "D*18") (pin "2") (pinfunction "2_2") (pintype "passive"))
      (node (ref "D*32") (pin "2") (pinfunction "2_2") (pintype "passive"))
      (node (ref "D*46") (pin "2") (pinfunction "2_2") (pintype "passive"))
      (node (ref "D*5") (pin "2") (pinfunction "2_2") (pintype "passive"))
      (node (ref "D*59") (pin "2") (pinfunction "2_2") (pintype "passive"))
      (node (ref "D*71") (pin "2") (pinfunction "2_2") (pintype "passive"))
      (node (ref "D*79") (pin "2") (pinfunction "2_2") (pintype "passive"))
    )
    (net (code "14") (name "KEY_POS6") (class "Default")
      (node (ref "D*19") (pin "2") (pinfunction "2_2") (pintype "passive"))
      (node (ref "D*33") (pin "2") (pinfunction "2_2") (pintype "passive"))
      (node (ref "D*47") (pin "2") (pinfunction "2_2") (pintype "passive"))
      (node (ref "D*6") (pin "2") (pinfunction "2_2") (pintype "passive"))
      (node (ref "D*60") (pin "2") (pinfunction "2_2") (pintype "passive"))
      (node (ref "D*72") (pin "2") (pinfunction "2_2") (pintype "passive"))
      (node (ref "D*80") (pin "2") (pinfunction "2_2") (pintype "passive"))
    )
    (net (code "15") (name "KEY_POS7") (class "Default")
      (node (ref "D*20") (pin "2") (pinfunction "2_2") (pintype "passive"))
      (node (ref "D*34") (pin "2") (pinfunction "2_2") (pintype "passive"))
      (node (ref "D*48") (pin "2") (pinfunction "2_2") (pintype "passive"))
      (node (ref "D*61") (pin "2") (pinfunction "2_2") (pintype "passive"))
      (node (ref "D*7") (pin "2") (pinfunction "2_2") (pintype "passive"))
      (node (ref "D*73") (pin "2") (pinfunction "2_2") (pintype "passive"))
      (node (ref "D*81") (pin "2") (pinfunction "2_2") (pintype "passive"))
    )
    (net (code "16") (name "KEY_POS8") (class "Default")
      (node (ref "D*21") (pin "2") (pinfunction "2_2") (pintype "passive"))
      (node (ref "D*35") (pin "2") (pinfunction "2_2") (pintype "passive"))
      (node (ref "D*49") (pin "2") (pinfunction "2_2") (pintype "passive"))
      (node (ref "D*62") (pin "2") (pinfunction "2_2") (pintype "passive"))
      (node (ref "D*74") (pin "2") (pinfunction "2_2") (pintype "passive"))
      (node (ref "D*8") (pin "2") (pinfunction "2_2") (pintype "passive"))
      (node (ref "D*82") (pin "2") (pinfunction "2_2") (pintype "passive"))
    )
    (net (code "17") (name "KEY_POS9") (class "Default")
      (node (ref "D*22") (pin "2") (pinfunction "2_2") (pintype "passive"))
      (node (ref "D*36") (pin "2") (pinfunction "2_2") (pintype "passive"))
      (node (ref "D*50") (pin "2") (pinfunction "2_2") (pintype "passive"))
      (node (ref "D*63") (pin "2") (pinfunction "2_2") (pintype "passive"))
      (node (ref "D*83") (pin "2") (pinfunction "2_2") (pintype "passive"))
      (node (ref "D*9") (pin "2") (pinfunction "2_2") (pintype "passive"))
    )
    (net (code "18") (name "KEY_POS10") (class "Default")
      (node (ref "D*10") (pin "2") (pinfunction "2_2") (pintype "passive"))
      (node (ref "D*23") (pin "2") (pinfunction "2_2") (pintype "passive"))
      (node (ref "D*37") (pin "2") (pinfunction "2_2") (pintype "passive"))
      (node (ref "D*51") (pin "2") (pinfunction "2_2") (pintype "passive"))
      (node (ref "D*64") (pin "2") (pinfunction "2_2") (pintype "passive"))
      (node (ref "D*84") (pin "2") (pinfunction "2_2") (pintype "passive"))
    )
    (net (code "19") (name "KEY_POS11") (class "Default")
      (node (ref "D*11") (pin "2") (pinfunction "2_2") (pintype "passive"))
      (node (ref "D*24") (pin "2") (pinfunction "2_2") (pintype "passive"))
      (node (ref "D*38") (pin "2") (pinfunction "2_2") (pintype "passive"))
      (node (ref "D*52") (pin "2") (pinfunction "2_2") (pintype "passive"))
      (node (ref "D*65") (pin "2") (pinfunction "2_2") (pintype "passive"))
      (node (ref "D*85") (pin "2") (pinfunction "2_2") (pintype "passive"))
    )
    (net (code "20") (name "KEY_POS12") (class "Default")
      (node (ref "D*12") (pin "2") (pinfunction "2_2") (pintype "passive"))
      (node (ref "D*25") (pin "2") (pinfunction "2_2") (pintype "passive"))
      (node (ref "D*39") (pin "2") (pinfunction "2_2") (pintype "passive"))
      (node (ref "D*53") (pin "2") (pinfunction "2_2") (pintype "passive"))
      (node (ref "D*66") (pin "2") (pinfunction "2_2") (pintype "passive"))
      (node (ref "D*86") (pin "2") (pinfunction "2_2") (pintype "passive"))
    )
    (net (code "21") (name "KEY_POS13") (class "Default")
      (node (ref "D*13") (pin "2") (pinfunction "2_2") (pintype "passive"))
      (node (ref "D*26") (pin "2") (pinfunction "2_2") (pintype "passive"))
      (node (ref "D*40") (pin "2") (pinfunction "2_2") (pintype "passive"))
      (node (ref "D*54") (pin "2") (pinfunction "2_2") (pintype "passive"))
      (node (ref "D*87") (pin "2") (pinfunction "2_2") (pintype "passive"))
    )
    (net (code "22") (name "KEY_POS14") (class "Default")
      (node (ref "D*27") (pin "2") (pinfunction "2_2") (pintype "passive"))
      (node (ref "D*41") (pin "2") (pinfunction "2_2") (pintype "passive"))
    )
    (net (code "23") (name "KEY_SEG1") (class "Default")
      (node (ref "SW1") (pin "1") (pinfunction "1_1") (pintype "passive"))
      (node (ref "SW10") (pin "1") (pinfunction "1_1") (pintype "passive"))
      (node (ref "SW11") (pin "1") (pinfunction "1_1") (pintype "passive"))
      (node (ref "SW12") (pin "1") (pinfunction "1_1") (pintype "passive"))
      (node (ref "SW13") (pin "1") (pinfunction "1_1") (pintype "passive"))
      (node (ref "SW2") (pin "1") (pinfunction "1_1") (pintype "passive"))
      (node (ref "SW3") (pin "1") (pinfunction "1_1") (pintype "passive"))
      (node (ref "SW4") (pin "1") (pinfunction "1_1") (pintype "passive"))
      (node (ref "SW5") (pin "1") (pinfunction "1_1") (pintype "passive"))
      (node (ref "SW6") (pin "1") (pinfunction "1_1") (pintype "passive"))
      (node (ref "SW7") (pin "1") (pinfunction "1_1") (pintype "passive"))
      (node (ref "SW8") (pin "1") (pinfunction "1_1") (pintype "passive"))
      (node (ref "SW9") (pin "1") (pinfunction "1_1") (pintype "passive"))
    )
    (net (code "24") (name "KEY_SEG2") (class "Default")
      (node (ref "SW14") (pin "1") (pinfunction "1_1") (pintype "passive"))
      (node (ref "SW15") (pin "1") (pinfunction "1_1") (pintype "passive"))
      (node (ref "SW16") (pin "1") (pinfunction "1_1") (pintype "passive"))
      (node (ref "SW17") (pin "1") (pinfunction "1_1") (pintype "passive"))
      (node (ref "SW18") (pin "1") (pinfunction "1_1") (pintype "passive"))
      (node (ref "SW19") (pin "1") (pinfunction "1_1") (pintype "passive"))
      (node (ref "SW20") (pin "1") (pinfunction "1_1") (pintype "passive"))
      (node (ref "SW21") (pin "1") (pinfunction "1_1") (pintype "passive"))
      (node (ref "SW22") (pin "1") (pinfunction "1_1") (pintype "passive"))
      (node (ref "SW23") (pin "1") (pinfunction "1_1") (pintype "passive"))
      (node (ref "SW24") (pin "1") (pinfunction "1_1") (pintype "passive"))
      (node (ref "SW25") (pin "1") (pinfunction "1_1") (pintype "passive"))
      (node (ref "SW26") (pin "1") (pinfunction "1_1") (pintype "passive"))
      (node (ref "SW27") (pin "1") (pinfunction "1_1") (pintype "passive"))
    )
    (net (code "25") (name "KEY_SEG3") (class "Default")
      (node (ref "SW28") (pin "1") (pinfunction "1_1") (pintype "passive"))
      (node (ref "SW29") (pin "1") (pinfunction "1_1") (pintype "passive"))
      (node (ref "SW30") (pin "1") (pinfunction "1_1") (pintype "passive"))
      (node (ref "SW31") (pin "1") (pinfunction "1_1") (pintype "passive"))
      (node (ref "SW32") (pin "1") (pinfunction "1_1") (pintype "passive"))
      (node (ref "SW33") (pin "1") (pinfunction "1_1") (pintype "passive"))
      (node (ref "SW34") (pin "1") (pinfunction "1_1") (pintype "passive"))
      (node (ref "SW35") (pin "1") (pinfunction "1_1") (pintype "passive"))
      (node (ref "SW36") (pin "1") (pinfunction "1_1") (pintype "passive"))
      (node (ref "SW37") (pin "1") (pinfunction "1_1") (pintype "passive"))
      (node (ref "SW38") (pin "1") (pinfunction "1_1") (pintype "passive"))
      (node (ref "SW39") (pin "1") (pinfunction "1_1") (pintype "passive"))
      (node (ref "SW40") (pin "1") (pinfunction "1_1") (pintype "passive"))
      (node (ref "SW41") (pin "1") (pinfunction "1_1") (pintype "passive"))
    )
    (net (code "26") (name "KEY_SEG4") (class "Default")
      (node (ref "SW42") (pin "1") (pinfunction "1_1") (pintype "passive"))
      (node (ref "SW43") (pin "1") (pinfunction "1_1") (pintype "passive"))
      (node (ref "SW44") (pin "1") (pinfunction "1_1") (pintype "passive"))
      (node (ref "SW45") (pin "1") (pinfunction "1_1") (pintype "passive"))
      (node (ref "SW46") (pin "1") (pinfunction "1_1") (pintype "passive"))
      (node (ref "SW47") (pin "1") (pinfunction "1_1") (pintype "passive"))
      (node (ref "SW48") (pin "1") (pinfunction "1_1") (pintype "passive"))
      (node (ref "SW49") (pin "1") (pinfunction "1_1") (pintype "passive"))
      (node (ref "SW50") (pin "1") (pinfunction "1_1") (pintype "passive"))
      (node (ref "SW51") (pin "1") (pinfunction "1_1") (pintype "passive"))
      (node (ref "SW52") (pin "1") (pinfunction "1_1") (pintype "passive"))
      (node (ref "SW53") (pin "1") (pinfunction "1_1") (pintype "passive"))
      (node (ref "SW54") (pin "1") (pinfunction "1_1") (pintype "passive"))
    )
    (net (code "27") (name "KEY_SEG5") (class "Default")
      (node (ref "SW55") (pin "1") (pinfunction "1_1") (pintype "passive"))
      (node (ref "SW56") (pin "1") (pinfunction "1_1") (pintype "passive"))
      (node (ref "SW57") (pin "1") (pinfunction "1_1") (pintype "passive"))
      (node (ref "SW58") (pin "1") (pinfunction "1_1") (pintype "passive"))
      (node (ref "SW59") (pin "1") (pinfunction "1_1") (pintype "passive"))
      (node (ref "SW60") (pin "1") (pinfunction "1_1") (pintype "passive"))
      (node (ref "SW61") (pin "1") (pinfunction "1_1") (pintype "passive"))
      (node (ref "SW62") (pin "1") (pinfunction "1_1") (pintype "passive"))
      (node (ref "SW63") (pin "1") (pinfunction "1_1") (pintype "passive"))
      (node (ref "SW64") (pin "1") (pinfunction "1_1") (pintype "passive"))
      (node (ref "SW65") (pin "1") (pinfunction "1_1") (pintype "passive"))
      (node (ref "SW66") (pin "1") (pinfunction "1_1") (pintype "passive"))
    )
    (net (code "28") (name "KEY_SEG6") (class "Default")
      (node (ref "SW67") (pin "1") (pinfunction "1_1") (pintype "passive"))
      (node (ref "SW68") (pin "1") (pinfunction "1_1") (pintype "passive"))
      (node (ref "SW69") (pin "1") (pinfunction "1_1") (pintype "passive"))
      (node (ref "SW70") (pin "1") (pinfunction "1_1") (pintype "passive"))
      (node (ref "SW71") (pin "1") (pinfunction "1_1") (pintype "passive"))
      (node (ref "SW72") (pin "1") (pinfunction "1_1") (pintype "passive"))
      (node (ref "SW73") (pin "1") (pinfunction "1_1") (pintype "passive"))
      (node (ref "SW74") (pin "1") (pinfunction "1_1") (pintype "passive"))
    )
    (net (code "29") (name "KEY_SEG7") (class "Default")
      (node (ref "SW75") (pin "1") (pinfunction "1_1") (pintype "passive"))
      (node (ref "SW76") (pin "1") (pinfunction "1_1") (pintype "passive"))
      (node (ref "SW77") (pin "1") (pinfunction "1_1") (pintype "passive"))
      (node (ref "SW78") (pin "1") (pinfunction "1_1") (pintype "passive"))
      (node (ref "SW79") (pin "1") (pinfunction "1_1") (pintype "passive"))
      (node (ref "SW80") (pin "1") (pinfunction "1_1") (pintype "passive"))
      (node (ref "SW81") (pin "1") (pinfunction "1_1") (pintype "passive"))
      (node (ref "SW82") (pin "1") (pinfunction "1_1") (pintype "passive"))
      (node (ref "SW83") (pin "1") (pinfunction "1_1") (pintype "passive"))
      (node (ref "SW84") (pin "1") (pinfunction "1_1") (pintype "passive"))
      (node (ref "SW85") (pin "1") (pinfunction "1_1") (pintype "passive"))
      (node (ref "SW86") (pin "1") (pinfunction "1_1") (pintype "passive"))
      (node (ref "SW87") (pin "1") (pinfunction "1_1") (pintype "passive"))
    )
    (net (code "30") (name "Net-(D*1-Pad1)") (class "Default")
      (node (ref "D*1") (pin "1") (pinfunction "1_1") (pintype "passive"))
      (node (ref "SW1") (pin "2") (pinfunction "2_2") (pintype "passive"))
    )
    (net (code "31") (name "Net-(D*2-Pad1)") (class "Default")
      (node (ref "D*2") (pin "1") (pinfunction "1_1") (pintype "passive"))
      (node (ref "SW2") (pin "2") (pinfunction "2_2") (pintype "passive"))
    )
    (net (code "32") (name "Net-(D*3-Pad1)") (class "Default")
      (node (ref "D*3") (pin "1") (pinfunction "1_1") (pintype "passive"))
      (node (ref "SW3") (pin "2") (pinfunction "2_2") (pintype "passive"))
    )
    (net (code "33") (name "Net-(D*4-Pad1)") (class "Default")
      (node (ref "D*4") (pin "1") (pinfunction "1_1") (pintype "passive"))
      (node (ref "SW4") (pin "2") (pinfunction "2_2") (pintype "passive"))
    )
    (net (code "34") (name "Net-(D*5-Pad1)") (class "Default")
      (node (ref "D*5") (pin "1") (pinfunction "1_1") (pintype "passive"))
      (node (ref "SW5") (pin "2") (pinfunction "2_2") (pintype "passive"))
    )
    (net (code "35") (name "Net-(D*6-Pad1)") (class "Default")
      (node (ref "D*6") (pin "1") (pinfunction "1_1") (pintype "passive"))
      (node (ref "SW6") (pin "2") (pinfunction "2_2") (pintype "passive"))
    )
    (net (code "36") (name "Net-(D*7-Pad1)") (class "Default")
      (node (ref "D*7") (pin "1") (pinfunction "1_1") (pintype "passive"))
      (node (ref "SW7") (pin "2") (pinfunction "2_2") (pintype "passive"))
    )
    (net (code "37") (name "Net-(D*8-Pad1)") (class "Default")
      (node (ref "D*8") (pin "1") (pinfunction "1_1") (pintype "passive"))
      (node (ref "SW8") (pin "2") (pinfunction "2_2") (pintype "passive"))
    )
    (net (code "38") (name "Net-(D*9-Pad1)") (class "Default")
      (node (ref "D*9") (pin "1") (pinfunction "1_1") (pintype "passive"))
      (node (ref "SW9") (pin "2") (pinfunction "2_2") (pintype "passive"))
    )
    (net (code "39") (name "Net-(D*10-Pad1)") (class "Default")
      (node (ref "D*10") (pin "1") (pinfunction "1_1") (pintype "passive"))
      (node (ref "SW10") (pin "2") (pinfunction "2_2") (pintype "passive"))
    )
    (net (code "40") (name "Net-(D*11-Pad1)") (class "Default")
      (node (ref "D*11") (pin "1") (pinfunction "1_1") (pintype "passive"))
      (node (ref "SW11") (pin "2") (pinfunction "2_2") (pintype "passive"))
    )
    (net (code "41") (name "Net-(D*12-Pad1)") (class "Default")
      (node (ref "D*12") (pin "1") (pinfunction "1_1") (pintype "passive"))
      (node (ref "SW12") (pin "2") (pinfunction "2_2") (pintype "passive"))
    )
    (net (code "42") (name "Net-(D*13-Pad1)") (class "Default")
      (node (ref "D*13") (pin "1") (pinfunction "1_1") (pintype "passive"))
      (node (ref "SW13") (pin "2") (pinfunction "2_2") (pintype "passive"))
    )
    (net (code "43") (name "Net-(D*14-Pad1)") (class "Default")
      (node (ref "D*14") (pin "1") (pinfunction "1_1") (pintype "passive"))
      (node (ref "SW14") (pin "2") (pinfunction "2_2") (pintype "passive"))
    )
    (net (code "44") (name "Net-(D*15-Pad1)") (class "Default")
      (node (ref "D*15") (pin "1") (pinfunction "1_1") (pintype "passive"))
      (node (ref "SW15") (pin "2") (pinfunction "2_2") (pintype "passive"))
    )
    (net (code "45") (name "Net-(D*16-Pad1)") (class "Default")
      (node (ref "D*16") (pin "1") (pinfunction "1_1") (pintype "passive"))
      (node (ref "SW16") (pin "2") (pinfunction "2_2") (pintype "passive"))
    )
    (net (code "46") (name "Net-(D*17-Pad1)") (class "Default")
      (node (ref "D*17") (pin "1") (pinfunction "1_1") (pintype "passive"))
      (node (ref "SW17") (pin "2") (pinfunction "2_2") (pintype "passive"))
    )
    (net (code "47") (name "Net-(D*18-Pad1)") (class "Default")
      (node (ref "D*18") (pin "1") (pinfunction "1_1") (pintype "passive"))
      (node (ref "SW18") (pin "2") (pinfunction "2_2") (pintype "passive"))
    )
    (net (code "48") (name "Net-(D*19-Pad1)") (class "Default")
      (node (ref "D*19") (pin "1") (pinfunction "1_1") (pintype "passive"))
      (node (ref "SW19") (pin "2") (pinfunction "2_2") (pintype "passive"))
    )
    (net (code "49") (name "Net-(D*20-Pad1)") (class "Default")
      (node (ref "D*20") (pin "1") (pinfunction "1_1") (pintype "passive"))
      (node (ref "SW20") (pin "2") (pinfunction "2_2") (pintype "passive"))
    )
    (net (code "50") (name "Net-(D*21-Pad1)") (class "Default")
      (node (ref "D*21") (pin "1") (pinfunction "1_1") (pintype "passive"))
      (node (ref "SW21") (pin "2") (pinfunction "2_2") (pintype "passive"))
    )
    (net (code "51") (name "Net-(D*22-Pad1)") (class "Default")
      (node (ref "D*22") (pin "1") (pinfunction "1_1") (pintype "passive"))
      (node (ref "SW22") (pin "2") (pinfunction "2_2") (pintype "passive"))
    )
    (net (code "52") (name "Net-(D*23-Pad1)") (class "Default")
      (node (ref "D*23") (pin "1") (pinfunction "1_1") (pintype "passive"))
      (node (ref "SW23") (pin "2") (pinfunction "2_2") (pintype "passive"))
    )
    (net (code "53") (name "Net-(D*24-Pad1)") (class "Default")
      (node (ref "D*24") (pin "1") (pinfunction "1_1") (pintype "passive"))
      (node (ref "SW24") (pin "2") (pinfunction "2_2") (pintype "passive"))
    )
    (net (code "54") (name "Net-(D*25-Pad1)") (class "Default")
      (node (ref "D*25") (pin "1") (pinfunction "1_1") (pintype "passive"))
      (node (ref "SW25") (pin "2") (pinfunction "2_2") (pintype "passive"))
    )
    (net (code "55") (name "Net-(D*26-Pad1)") (class "Default")
      (node (ref "D*26") (pin "1") (pinfunction "1_1") (pintype "passive"))
      (node (ref "SW26") (pin "2") (pinfunction "2_2") (pintype "passive"))
    )
    (net (code "56") (name "Net-(D*27-Pad1)") (class "Default")
      (node (ref "D*27") (pin "1") (pinfunction "1_1") (pintype "passive"))
      (node (ref "SW27") (pin "2") (pinfunction "2_2") (pintype "passive"))
    )
    (net (code "57") (name "Net-(D*28-Pad1)") (class "Default")
      (node (ref "D*28") (pin "1") (pinfunction "1_1") (pintype "passive"))
      (node (ref "SW28") (pin "2") (pinfunction "2_2") (pintype "passive"))
    )
    (net (code "58") (name "Net-(D*29-Pad1)") (class "Default")
      (node (ref "D*29") (pin "1") (pinfunction "1_1") (pintype "passive"))
      (node (ref "SW29") (pin "2") (pinfunction "2_2") (pintype "passive"))
    )
    (net (code "59") (name "Net-(D*30-Pad1)") (class "Default")
      (node (ref "D*30") (pin "1") (pinfunction "1_1") (pintype "passive"))
      (node (ref "SW30") (pin "2") (pinfunction "2_2") (pintype "passive"))
    )
    (net (code "60") (name "Net-(D*31-Pad1)") (class "Default")
      (node (ref "D*31") (pin "1") (pinfunction "1_1") (pintype "passive"))
      (node (ref "SW31") (pin "2") (pinfunction "2_2") (pintype "passive"))
    )
    (net (code "61") (name "Net-(D*32-Pad1)") (class "Default")
      (node (ref "D*32") (pin "1") (pinfunction "1_1") (pintype "passive"))
      (node (ref "SW32") (pin "2") (pinfunction "2_2") (pintype "passive"))
    )
    (net (code "62") (name "Net-(D*33-Pad1)") (class "Default")
      (node (ref "D*33") (pin "1") (pinfunction "1_1") (pintype "passive"))
      (node (ref "SW33") (pin "2") (pinfunction "2_2") (pintype "passive"))
    )
    (net (code "63") (name "Net-(D*34-Pad1)") (class "Default")
      (node (ref "D*34") (pin "1") (pinfunction "1_1") (pintype "passive"))
      (node (ref "SW34") (pin "2") (pinfunction "2_2") (pintype "passive"))
    )
    (net (code "64") (name "Net-(D*35-Pad1)") (class "Default")
      (node (ref "D*35") (pin "1") (pinfunction "1_1") (pintype "passive"))
      (node (ref "SW35") (pin "2") (pinfunction "2_2") (pintype "passive"))
    )
    (net (code "65") (name "Net-(D*36-Pad1)") (class "Default")
      (node (ref "D*36") (pin "1") (pinfunction "1_1") (pintype "passive"))
      (node (ref "SW36") (pin "2") (pinfunction "2_2") (pintype "passive"))
    )
    (net (code "66") (name "Net-(D*37-Pad1)") (class "Default")
      (node (ref "D*37") (pin "1") (pinfunction "1_1") (pintype "passive"))
      (node (ref "SW37") (pin "2") (pinfunction "2_2") (pintype "passive"))
    )
    (net (code "67") (name "Net-(D*38-Pad1)") (class "Default")
      (node (ref "D*38") (pin "1") (pinfunction "1_1") (pintype "passive"))
      (node (ref "SW38") (pin "2") (pinfunction "2_2") (pintype "passive"))
    )
    (net (code "68") (name "Net-(D*39-Pad1)") (class "Default")
      (node (ref "D*39") (pin "1") (pinfunction "1_1") (pintype "passive"))
      (node (ref "SW39") (pin "2") (pinfunction "2_2") (pintype "passive"))
    )
    (net (code "69") (name "Net-(D*40-Pad1)") (class "Default")
      (node (ref "D*40") (pin "1") (pinfunction "1_1") (pintype "passive"))
      (node (ref "SW40") (pin "2") (pinfunction "2_2") (pintype "passive"))
    )
    (net (code "70") (name "Net-(D*41-Pad1)") (class "Default")
      (node (ref "D*41") (pin "1") (pinfunction "1_1") (pintype "passive"))
      (node (ref "SW41") (pin "2") (pinfunction "2_2") (pintype "passive"))
    )
    (net (code "71") (name "Net-(D*42-Pad1)") (class "Default")
      (node (ref "D*42") (pin "1") (pinfunction "1_1") (pintype "passive"))
      (node (ref "SW42") (pin "2") (pinfunction "2_2") (pintype "passive"))
    )
    (net (code "72") (name "Net-(D*43-Pad1)") (class "Default")
      (node (ref "D*43") (pin "1") (pinfunction "1_1") (pintype "passive"))
      (node (ref "SW43") (pin "2") (pinfunction "2_2") (pintype "passive"))
    )
    (net (code "73") (name "Net-(D*44-Pad1)") (class "Default")
      (node (ref "D*44") (pin "1") (pinfunction "1_1") (pintype "passive"))
      (node (ref "SW44") (pin "2") (pinfunction "2_2") (pintype "passive"))
    )
    (net (code "74") (name "Net-(D*45-Pad1)") (class "Default")
      (node (ref "D*45") (pin "1") (pinfunction "1_1") (pintype "passive"))
      (node (ref "SW45") (pin "2") (pinfunction "2_2") (pintype "passive"))
    )
    (net (code "75") (name "Net-(D*46-Pad1)") (class "Default")
      (node (ref "D*46") (pin "1") (pinfunction "1_1") (pintype "passive"))
      (node (ref "SW46") (pin "2") (pinfunction "2_2") (pintype "passive"))
    )
    (net (code "76") (name "Net-(D*47-Pad1)") (class "Default")
      (node (ref "D*47") (pin "1") (pinfunction "1_1") (pintype "passive"))
      (node (ref "SW47") (pin "2") (pinfunction "2_2") (pintype "passive"))
    )
    (net (code "77") (name "Net-(D*48-Pad1)") (class "Default")
      (node (ref "D*48") (pin "1") (pinfunction "1_1") (pintype "passive"))
      (node (ref "SW48") (pin "2") (pinfunction "2_2") (pintype "passive"))
    )
    (net (code "78") (name "Net-(D*49-Pad1)") (class "Default")
      (node (ref "D*49") (pin "1") (pinfunction "1_1") (pintype "passive"))
      (node (ref "SW49") (pin "2") (pinfunction "2_2") (pintype "passive"))
    )
    (net (code "79") (name "Net-(D*50-Pad1)") (class "Default")
      (node (ref "D*50") (pin "1") (pinfunction "1_1") (pintype "passive"))
      (node (ref "SW50") (pin "2") (pinfunction "2_2") (pintype "passive"))
    )
    (net (code "80") (name "Net-(D*51-Pad1)") (class "Default")
      (node (ref "D*51") (pin "1") (pinfunction "1_1") (pintype "passive"))
      (node (ref "SW51") (pin "2") (pinfunction "2_2") (pintype "passive"))
    )
    (net (code "81") (name "Net-(D*52-Pad1)") (class "Default")
      (node (ref "D*52") (pin "1") (pinfunction "1_1") (pintype "passive"))
      (node (ref "SW52") (pin "2") (pinfunction "2_2") (pintype "passive"))
    )
    (net (code "82") (name "Net-(D*53-Pad1)") (class "Default")
      (node (ref "D*53") (pin "1") (pinfunction "1_1") (pintype "passive"))
      (node (ref "SW53") (pin "2") (pinfunction "2_2") (pintype "passive"))
    )
    (net (code "83") (name "Net-(D*54-Pad1)") (class "Default")
      (node (ref "D*54") (pin "1") (pinfunction "1_1") (pintype "passive"))
      (node (ref "SW54") (pin "2") (pinfunction "2_2") (pintype "passive"))
    )
    (net (code "84") (name "Net-(D*55-Pad1)") (class "Default")
      (node (ref "D*55") (pin "1") (pinfunction "1_1") (pintype "passive"))
      (node (ref "SW55") (pin "2") (pinfunction "2_2") (pintype "passive"))
    )
    (net (code "85") (name "Net-(D*56-Pad1)") (class "Default")
      (node (ref "D*56") (pin "1") (pinfunction "1_1") (pintype "passive"))
      (node (ref "SW56") (pin "2") (pinfunction "2_2") (pintype "passive"))
    )
    (net (code "86") (name "Net-(D*57-Pad1)") (class "Default")
      (node (ref "D*57") (pin "1") (pinfunction "1_1") (pintype "passive"))
      (node (ref "SW57") (pin "2") (pinfunction "2_2") (pintype "passive"))
    )
    (net (code "87") (name "Net-(D*58-Pad1)") (class "Default")
      (node (ref "D*58") (pin "1") (pinfunction "1_1") (pintype "passive"))
      (node (ref "SW58") (pin "2") (pinfunction "2_2") (pintype "passive"))
    )
    (net (code "88") (name "Net-(D*59-Pad1)") (class "Default")
      (node (ref "D*59") (pin "1") (pinfunction "1_1") (pintype "passive"))
      (node (ref "SW59") (pin "2") (pinfunction "2_2") (pintype "passive"))
    )
    (net (code "89") (name "Net-(D*60-Pad1)") (class "Default")
      (node (ref "D*60") (pin "1") (pinfunction "1_1") (pintype "passive"))
      (node (ref "SW60") (pin "2") (pinfunction "2_2") (pintype "passive"))
    )
    (net (code "90") (name "Net-(D*61-Pad1)") (class "Default")
      (node (ref "D*61") (pin "1") (pinfunction "1_1") (pintype "passive"))
      (node (ref "SW61") (pin "2") (pinfunction "2_2") (pintype "passive"))
    )
    (net (code "91") (name "Net-(D*62-Pad1)") (class "Default")
      (node (ref "D*62") (pin "1") (pinfunction "1_1") (pintype "passive"))
      (node (ref "SW62") (pin "2") (pinfunction "2_2") (pintype "passive"))
    )
    (net (code "92") (name "Net-(D*63-Pad1)") (class "Default")
      (node (ref "D*63") (pin "1") (pinfunction "1_1") (pintype "passive"))
      (node (ref "SW63") (pin "2") (pinfunction "2_2") (pintype "passive"))
    )
    (net (code "93") (name "Net-(D*64-Pad1)") (class "Default")
      (node (ref "D*64") (pin "1") (pinfunction "1_1") (pintype "passive"))
      (node (ref "SW64") (pin "2") (pinfunction "2_2") (pintype "passive"))
    )
    (net (code "94") (name "Net-(D*65-Pad1)") (class "Default")
      (node (ref "D*65") (pin "1") (pinfunction "1_1") (pintype "passive"))
      (node (ref "SW65") (pin "2") (pinfunction "2_2") (pintype "passive"))
    )
    (net (code "95") (name "Net-(D*66-Pad1)") (class "Default")
      (node (ref "D*66") (pin "1") (pinfunction "1_1") (pintype "passive"))
      (node (ref "SW66") (pin "2") (pinfunction "2_2") (pintype "passive"))
    )
    (net (code "96") (name "Net-(D*67-Pad1)") (class "Default")
      (node (ref "D*67") (pin "1") (pinfunction "1_1") (pintype "passive"))
      (node (ref "SW67") (pin "2") (pinfunction "2_2") (pintype "passive"))
    )
    (net (code "97") (name "Net-(D*68-Pad1)") (class "Default")
      (node (ref "D*68") (pin "1") (pinfunction "1_1") (pintype "passive"))
      (node (ref "SW68") (pin "2") (pinfunction "2_2") (pintype "passive"))
    )
    (net (code "98") (name "Net-(D*69-Pad1)") (class "Default")
      (node (ref "D*69") (pin "1") (pinfunction "1_1") (pintype "passive"))
      (node (ref "SW69") (pin "2") (pinfunction "2_2") (pintype "passive"))
    )
    (net (code "99") (name "Net-(D*70-Pad1)") (class "Default")
      (node (ref "D*70") (pin "1") (pinfunction "1_1") (pintype "passive"))
      (node (ref "SW70") (pin "2") (pinfunction "2_2") (pintype "passive"))
    )
    (net (code "100") (name "Net-(D*71-Pad1)") (class "Default")
      (node (ref "D*71") (pin "1") (pinfunction "1_1") (pintype "passive"))
      (node (ref "SW71") (pin "2") (pinfunction "2_2") (pintype "passive"))
    )
    (net (code "101") (name "Net-(D*72-Pad1)") (class "Default")
      (node (ref "D*72") (pin "1") (pinfunction "1_1") (pintype "passive"))
      (node (ref "SW72") (pin "2") (pinfunction "2_2") (pintype "passive"))
    )
    (net (code "102") (name "Net-(D*73-Pad1)") (class "Default")
      (node (ref "D*73") (pin "1") (pinfunction "1_1") (pintype "passive"))
      (node (ref "SW73") (pin "2") (pinfunction "2_2") (pintype "passive"))
    )
    (net (code "103") (name "Net-(D*74-Pad1)") (class "Default")
      (node (ref "D*74") (pin "1") (pinfunction "1_1") (pintype "passive"))
      (node (ref "SW74") (pin "2") (pinfunction "2_2") (pintype "passive"))
    )
    (net (code "104") (name "Net-(D*75-Pad1)") (class "Default")
      (node (ref "D*75") (pin "1") (pinfunction "1_1") (pintype "passive"))
      (node (ref "SW75") (pin "2") (pinfunction "2_2") (pintype "passive"))
    )
    (net (code "105") (name "Net-(D*76-Pad1)") (class "Default")
      (node (ref "D*76") (pin "1") (pinfunction "1_1") (pintype "passive"))
      (node (ref "SW76") (pin "2") (pinfunction "2_2") (pintype "passive"))
    )
    (net (code "106") (name "Net-(D*77-Pad1)") (class "Default")
      (node (ref "D*77") (pin "1") (pinfunction "1_1") (pintype "passive"))
      (node (ref "SW77") (pin "2") (pinfunction "2_2") (pintype "passive"))
    )
    (net (code "107") (name "Net-(D*78-Pad1)") (class "Default")
      (node (ref "D*78") (pin "1") (pinfunction "1_1") (pintype "passive"))
      (node (ref "SW78") (pin "2") (pinfunction "2_2") (pintype "passive"))
    )
    (net (code "108") (name "Net-(D*79-Pad1)") (class "Default")
      (node (ref "D*79") (pin "1") (pinfunction "1_1") (pintype "passive"))
      (node (ref "SW79") (pin "2") (pinfunction "2_2") (pintype "passive"))
    )
    (net (code "109") (name "Net-(D*80-Pad1)") (class "Default")
      (node (ref "D*80") (pin "1") (pinfunction "1_1") (pintype "passive"))
      (node (ref "SW80") (pin "2") (pinfunction "2_2") (pintype "passive"))
    )
    (net (code "110") (name "Net-(D*81-Pad1)") (class "Default")
      (node (ref "D*81") (pin "1") (pinfunction "1_1") (pintype "passive"))
      (node (ref "SW81") (pin "2") (pinfunction "2_2") (pintype "passive"))
    )
    (net (code "111") (name "Net-(D*82-Pad1)") (class "Default")
      (node (ref "D*82") (pin "1") (pinfunction "1_1") (pintype "passive"))
      (node (ref "SW82") (pin "2") (pinfunction "2_2") (pintype "passive"))
    )
    (net (code "112") (name "Net-(D*83-Pad1)") (class "Default")
      (node (ref "D*83") (pin "1") (pinfunction "1_1") (pintype "passive"))
      (node (ref "SW83") (pin "2") (pinfunction "2_2") (pintype "passive"))
    )
    (net (code "113") (name "Net-(D*84-Pad1)") (class "Default")
      (node (ref "D*84") (pin "1") (pinfunction "1_1") (pintype "passive"))
      (node (ref "SW84") (pin "2") (pinfunction "2_2") (pintype "passive"))
    )
    (net (code "114") (name "Net-(D*85-Pad1)") (class "Default")
      (node (ref "D*85") (pin "1") (pinfunction "1_1") (pintype "passive"))
      (node (ref "SW85") (pin "2") (pinfunction "2_2") (pintype "passive"))
    )
    (net (code "115") (name "Net-(D*86-Pad1)") (class "Default")
      (node (ref "D*86") (pin "1") (pinfunction "1_1") (pintype "passive"))
      (node (ref "SW86") (pin "2") (pinfunction "2_2") (pintype "passive"))
    )
    (net (code "116") (name "Net-(D*87-Pad1)") (class "Default")
      (node (ref "D*87") (pin "1") (pinfunction "1_1") (pintype "passive"))
      (node (ref "SW87") (pin "2") (pinfunction "2_2") (pintype "passive"))
    )
    (net (code "117") (name "Net-(SW1-DOUT)") (class "Default")
      (node (ref "SW1") (pin "4") (pinfunction "DOUT_4") (pintype "passive"))
      (node (ref "SW2") (pin "6") (pinfunction "DIN_6") (pintype "passive"))
    )
    (net (code "118") (name "Net-(SW2-DOUT)") (class "Default")
      (node (ref "SW2") (pin "4") (pinfunction "DOUT_4") (pintype "passive"))
      (node (ref "SW3") (pin "6") (pinfunction "DIN_6") (pintype "passive"))
    )
    (net (code "119") (name "Net-(SW3-DOUT)") (class "Default")
      (node (ref "SW3") (pin "4") (pinfunction "DOUT_4") (pintype "passive"))
      (node (ref "SW4") (pin "6") (pinfunction "DIN_6") (pintype "passive"))
    )
    (net (code "120") (name "Net-(SW4-DOUT)") (class "Default")
      (node (ref "SW4") (pin "4") (pinfunction "DOUT_4") (pintype "passive"))
      (node (ref "SW5") (pin "6") (pinfunction "DIN_6") (pintype "passive"))
    )
    (net (code "121") (name "Net-(SW5-DOUT)") (class "Default")
      (node (ref "SW5") (pin "4") (pinfunction "DOUT_4") (pintype "passive"))
      (node (ref "SW6") (pin "6") (pinfunction "DIN_6") (pintype "passive"))
    )
    (net (code "122") (name "Net-(SW6-DOUT)") (class "Default")
      (node (ref "SW6") (pin "4") (pinfunction "DOUT_4") (pintype "passive"))
      (node (ref "SW7") (pin "6") (pinfunction "DIN_6") (pintype "passive"))
    )
    (net (code "123") (name "Net-(SW7-DOUT)") (class "Default")
      (node (ref "SW7") (pin "4") (pinfunction "DOUT_4") (pintype "passive"))
      (node (ref "SW8") (pin "6") (pinfunction "DIN_6") (pintype "passive"))
    )
    (net (code "124") (name "Net-(SW8-DOUT)") (class "Default")
      (node (ref "SW8") (pin "4") (pinfunction "DOUT_4") (pintype "passive"))
      (node (ref "SW9") (pin "6") (pinfunction "DIN_6") (pintype "passive"))
    )
    (net (code "125") (name "Net-(SW10-DIN)") (class "Default")
      (node (ref "SW10") (pin "6") (pinfunction "DIN_6") (pintype "passive"))
      (node (ref "SW9") (pin "4") (pinfunction "DOUT_4") (pintype "passive"))
    )
    (net (code "126") (name "Net-(SW10-DOUT)") (class "Default")
      (node (ref "SW10") (pin "4") (pinfunction "DOUT_4") (pintype "passive"))
      (node (ref "SW11") (pin "6") (pinfunction "DIN_6") (pintype "passive"))
    )
    (net (code "127") (name "Net-(SW11-DOUT)") (class "Default")
      (node (ref "SW11") (pin "4") (pinfunction "DOUT_4") (pintype "passive"))
      (node (ref "SW12") (pin "6") (pinfunction "DIN_6") (pintype "passive"))
    )
    (net (code "128") (name "Net-(SW12-DOUT)") (class "Default")
      (node (ref "SW12") (pin "4") (pinfunction "DOUT_4") (pintype "passive"))
      (node (ref "SW13") (pin "6") (pinfunction "DIN_6") (pintype "passive"))
    )
    (net (code "129") (name "Net-(SW14-DOUT)") (class "Default")
      (node (ref "SW14") (pin "4") (pinfunction "DOUT_4") (pintype "passive"))
      (node (ref "SW15") (pin "6") (pinfunction "DIN_6") (pintype "passive"))
    )
    (net (code "130") (name "Net-(SW15-DOUT)") (class "Default")
      (node (ref "SW15") (pin "4") (pinfunction "DOUT_4") (pintype "passive"))
      (node (ref "SW16") (pin "6") (pinfunction "DIN_6") (pintype "passive"))
    )
    (net (code "131") (name "Net-(SW16-DOUT)") (class "Default")
      (node (ref "SW16") (pin "4") (pinfunction "DOUT_4") (pintype "passive"))
      (node (ref "SW17") (pin "6") (pinfunction "DIN_6") (pintype "passive"))
    )
    (net (code "132") (name "Net-(SW17-DOUT)") (class "Default")
      (node (ref "SW17") (pin "4") (pinfunction "DOUT_4") (pintype "passive"))
      (node (ref "SW18") (pin "6") (pinfunction "DIN_6") (pintype "passive"))
    )
    (net (code "133") (name "Net-(SW18-DOUT)") (class "Default")
      (node (ref "SW18") (pin "4") (pinfunction "DOUT_4") (pintype "passive"))
      (node (ref "SW19") (pin "6") (pinfunction "DIN_6") (pintype "passive"))
    )
    (net (code "134") (name "Net-(SW19-DOUT)") (class "Default")
      (node (ref "SW19") (pin "4") (pinfunction "DOUT_4") (pintype "passive"))
      (node (ref "SW20") (pin "6") (pinfunction "DIN_6") (pintype "passive"))
    )
    (net (code "135") (name "Net-(SW20-DOUT)") (class "Default")
      (node (ref "SW20") (pin "4") (pinfunction "DOUT_4") (pintype "passive"))
      (node (ref "SW21") (pin "6") (pinfunction "DIN_6") (pintype "passive"))
    )
    (net (code "136") (name "Net-(SW21-DOUT)") (class "Default")
      (node (ref "SW21") (pin "4") (pinfunction "DOUT_4") (pintype "passive"))
      (node (ref "SW22") (pin "6") (pinfunction "DIN_6") (pintype "passive"))
    )
    (net (code "137") (name "Net-(SW22-DOUT)") (class "Default")
      (node (ref "SW22") (pin "4") (pinfunction "DOUT_4") (pintype "passive"))
      (node (ref "SW23") (pin "6") (pinfunction "DIN_6") (pintype "passive"))
    )
    (net (code "138") (name "Net-(SW23-DOUT)") (class "Default")
      (node (ref "SW23") (pin "4") (pinfunction "DOUT_4") (pintype "passive"))
      (node (ref "SW24") (pin "6") (pinfunction "DIN_6") (pintype "passive"))
    )
    (net (code "139") (name "Net-(SW24-DOUT)") (class "Default")
      (node (ref "SW24") (pin "4") (pinfunction "DOUT_4") (pintype "passive"))
      (node (ref "SW25") (pin "6") (pinfunction "DIN_6") (pintype "passive"))
    )
    (net (code "140") (name "Net-(SW25-DOUT)") (class "Default")
      (node (ref "SW25") (pin "4") (pinfunction "DOUT_4") (pintype "passive"))
      (node (ref "SW26") (pin "6") (pinfunction "DIN_6") (pintype "passive"))
    )
    (net (code "141") (name "Net-(SW26-DOUT)") (class "Default")
      (node (ref "SW26") (pin "4") (pinfunction "DOUT_4") (pintype "passive"))
      (node (ref "SW27") (pin "6") (pinfunction "DIN_6") (pintype "passive"))
    )
    (net (code "142") (name "Net-(SW28-DOUT)") (class "Default")
      (node (ref "SW28") (pin "4") (pinfunction "DOUT_4") (pintype "passive"))
      (node (ref "SW29") (pin "6") (pinfunction "DIN_6") (pintype "passive"))
    )
    (net (code "143") (name "Net-(SW29-DOUT)") (class "Default")
      (node (ref "SW29") (pin "4") (pinfunction "DOUT_4") (pintype "passive"))
      (node (ref "SW30") (pin "6") (pinfunction "DIN_6") (pintype "passive"))
    )
    (net (code "144") (name "Net-(SW30-DOUT)") (class "Default")
      (node (ref "SW30") (pin "4") (pinfunction "DOUT_4") (pintype "passive"))
      (node (ref "SW31") (pin "6") (pinfunction "DIN_6") (pintype "passive"))
    )
    (net (code "145") (name "Net-(SW31-DOUT)") (class "Default")
      (node (ref "SW31") (pin "4") (pinfunction "DOUT_4") (pintype "passive"))
      (node (ref "SW32") (pin "6") (pinfunction "DIN_6") (pintype "passive"))
    )
    (net (code "146") (name "Net-(SW32-DOUT)") (class "Default")
      (node (ref "SW32") (pin "4") (pinfunction "DOUT_4") (pintype "passive"))
      (node (ref "SW33") (pin "6") (pinfunction "DIN_6") (pintype "passive"))
    )
    (net (code "147") (name "Net-(SW33-DOUT)") (class "Default")
      (node (ref "SW33") (pin "4") (pinfunction "DOUT_4") (pintype "passive"))
      (node (ref "SW34") (pin "6") (pinfunction "DIN_6") (pintype "passive"))
    )
    (net (code "148") (name "Net-(SW34-DOUT)") (class "Default")
      (node (ref "SW34") (pin "4") (pinfunction "DOUT_4") (pintype "passive"))
      (node (ref "SW35") (pin "6") (pinfunction "DIN_6") (pintype "passive"))
    )
    (net (code "149") (name "Net-(SW35-DOUT)") (class "Default")
      (node (ref "SW35") (pin "4") (pinfunction "DOUT_4") (pintype "passive"))
      (node (ref "SW36") (pin "6") (pinfunction "DIN_6") (pintype "passive"))
    )
    (net (code "150") (name "Net-(SW36-DOUT)") (class "Default")
      (node (ref "SW36") (pin "4") (pinfunction "DOUT_4") (pintype "passive"))
      (node (ref "SW37") (pin "6") (pinfunction "DIN_6") (pintype "passive"))
    )
    (net (code "151") (name "Net-(SW37-DOUT)") (class "Default")
      (node (ref "SW37") (pin "4") (pinfunction "DOUT_4") (pintype "passive"))
      (node (ref "SW38") (pin "6") (pinfunction "DIN_6") (pintype "passive"))
    )
    (net (code "152") (name "Net-(SW38-DOUT)") (class "Default")
      (node (ref "SW38") (pin "4") (pinfunction "DOUT_4") (pintype "passive"))
      (node (ref "SW39") (pin "6") (pinfunction "DIN_6") (pintype "passive"))
    )
    (net (code "153") (name "Net-(SW39-DOUT)") (class "Default")
      (node (ref "SW39") (pin "4") (pinfunction "DOUT_4") (pintype "passive"))
      (node (ref "SW40") (pin "6") (pinfunction "DIN_6") (pintype "passive"))
    )
    (net (code "154") (name "Net-(SW40-DOUT)") (class "Default")
      (node (ref "SW40") (pin "4") (pinfunction "DOUT_4") (pintype "passive"))
      (node (ref "SW41") (pin "6") (pinfunction "DIN_6") (pintype "passive"))
    )
    (net (code "155") (name "Net-(SW42-DOUT)") (class "Default")
      (node (ref "SW42") (pin "4") (pinfunction "DOUT_4") (pintype "passive"))
      (node (ref "SW43") (pin "6") (pinfunction "DIN_6") (pintype "passive"))
    )
    (net (code "156") (name "Net-(SW43-DOUT)") (class "Default")
      (node (ref "SW43") (pin "4") (pinfunction "DOUT_4") (pintype "passive"))
      (node (ref "SW44") (pin "6") (pinfunction "DIN_6") (pintype "passive"))
    )
    (net (code "157") (name "Net-(SW44-DOUT)") (class "Default")
      (node (ref "SW44") (pin "4") (pinfunction "DOUT_4") (pintype "passive"))
      (node (ref "SW45") (pin "6") (pinfunction "DIN_6") (pintype "passive"))
    )
    (net (code "158") (name "Net-(SW45-DOUT)") (class "Default")
      (node (ref "SW45") (pin "4") (pinfunction "DOUT_4") (pintype "passive"))
      (node (ref "SW46") (pin "6") (pinfunction "DIN_6") (pintype "passive"))
    )
    (net (code "159") (name "Net-(SW46-DOUT)") (class "Default")
      (node (ref "SW46") (pin "4") (pinfunction "DOUT_4") (pintype "passive"))
      (node (ref "SW47") (pin "6") (pinfunction "DIN_6") (pintype "passive"))
    )
    (net (code "160") (name "Net-(SW47-DOUT)") (class "Default")
      (node (ref "SW47") (pin "4") (pinfunction "DOUT_4") (pintype "passive"))
      (node (ref "SW48") (pin "6") (pinfunction "DIN_6") (pintype "passive"))
    )
    (net (code "161") (name "Net-(SW48-DOUT)") (class "Default")
      (node (ref "SW48") (pin "4") (pinfunction "DOUT_4") (pintype "passive"))
      (node (ref "SW49") (pin "6") (pinfunction "DIN_6") (pintype "passive"))
    )
    (net (code "162") (name "Net-(SW49-DOUT)") (class "Default")
      (node (ref "SW49") (pin "4") (pinfunction "DOUT_4") (pintype "passive"))
      (node (ref "SW50") (pin "6") (pinfunction "DIN_6") (pintype "passive"))
    )
    (net (code "163") (name "Net-(SW50-DOUT)") (class "Default")
      (node (ref "SW50") (pin "4") (pinfunction "DOUT_4") (pintype "passive"))
      (node (ref "SW51") (pin "6") (pinfunction "DIN_6") (pintype "passive"))
    )
    (net (code "164") (name "Net-(SW51-DOUT)") (class "Default")
      (node (ref "SW51") (pin "4") (pinfunction "DOUT_4") (pintype "passive"))
      (node (ref "SW52") (pin "6") (pinfunction "DIN_6") (pintype "passive"))
    )
    (net (code "165") (name "Net-(SW52-DOUT)") (class "Default")
      (node (ref "SW52") (pin "4") (pinfunction "DOUT_4") (pintype "passive"))
      (node (ref "SW53") (pin "6") (pinfunction "DIN_6") (pintype "passive"))
    )
    (net (code "166") (name "Net-(SW53-DOUT)") (class "Default")
      (node (ref "SW53") (pin "4") (pinfunction "DOUT_4") (pintype "passive"))
      (node (ref "SW54") (pin "6") (pinfunction "DIN_6") (pintype "passive"))
    )
    (net (code "167") (name "Net-(SW55-DOUT)") (class "Default")
      (node (ref "SW55") (pin "4") (pinfunction "DOUT_4") (pintype "passive"))
      (node (ref "SW56") (pin "6") (pinfunction "DIN_6") (pintype "passive"))
    )
    (net (code "168") (name "Net-(SW56-DOUT)") (class "Default")
      (node (ref "SW56") (pin "4") (pinfunction "DOUT_4") (pintype "passive"))
      (node (ref "SW57") (pin "6") (pinfunction "DIN_6") (pintype "passive"))
    )
    (net (code "169") (name "Net-(SW57-DOUT)") (class "Default")
      (node (ref "SW57") (pin "4") (pinfunction "DOUT_4") (pintype "passive"))
      (node (ref "SW58") (pin "6") (pinfunction "DIN_6") (pintype "passive"))
    )
    (net (code "170") (name "Net-(SW58-DOUT)") (class "Default")
      (node (ref "SW58") (pin "4") (pinfunction "DOUT_4") (pintype "passive"))
      (node (ref "SW59") (pin "6") (pinfunction "DIN_6") (pintype "passive"))
    )
    (net (code "171") (name "Net-(SW59-DOUT)") (class "Default")
      (node (ref "SW59") (pin "4") (pinfunction "DOUT_4") (pintype "passive"))
      (node (ref "SW60") (pin "6") (pinfunction "DIN_6") (pintype "passive"))
    )
    (net (code "172") (name "Net-(SW60-DOUT)") (class "Default")
      (node (ref "SW60") (pin "4") (pinfunction "DOUT_4") (pintype "passive"))
      (node (ref "SW61") (pin "6") (pinfunction "DIN_6") (pintype "passive"))
    )
    (net (code "173") (name "Net-(SW61-DOUT)") (class "Default")
      (node (ref "SW61") (pin "4") (pinfunction "DOUT_4") (pintype "passive"))
      (node (ref "SW62") (pin "6") (pinfunction "DIN_6") (pintype "passive"))
    )
    (net (code "174") (name "Net-(SW62-DOUT)") (class "Default")
      (node (ref "SW62") (pin "4") (pinfunction "DOUT_4") (pintype "passive"))
      (node (ref "SW63") (pin "6") (pinfunction "DIN_6") (pintype "passive"))
    )
    (net (code "175") (name "Net-(SW63-DOUT)") (class "Default")
      (node (ref "SW63") (pin "4") (pinfunction "DOUT_4") (pintype "passive"))
      (node (ref "SW64") (pin "6") (pinfunction "DIN_6") (pintype "passive"))
    )
    (net (code "176") (name "Net-(SW64-DOUT)") (class "Default")
      (node (ref "SW64") (pin "4") (pinfunction "DOUT_4") (pintype "passive"))
      (node (ref "SW65") (pin "6") (pinfunction "DIN_6") (pintype "passive"))
    )
    (net (code "177") (name "Net-(SW65-DOUT)") (class "Default")
      (node (ref "SW65") (pin "4") (pinfunction "DOUT_4") (pintype "passive"))
      (node (ref "SW66") (pin "6") (pinfunction "DIN_6") (pintype "passive"))
    )
    (net (code "178") (name "Net-(SW67-DOUT)") (class "Default")
      (node (ref "SW67") (pin "4") (pinfunction "DOUT_4") (pintype "passive"))
      (node (ref "SW68") (pin "6") (pinfunction "DIN_6") (pintype "passive"))
    )
    (net (code "179") (name "Net-(SW68-DOUT)") (class "Default")
      (node (ref "SW68") (pin "4") (pinfunction "DOUT_4") (pintype "passive"))
      (node (ref "SW69") (pin "6") (pinfunction "DIN_6") (pintype "passive"))
    )
    (net (code "180") (name "Net-(SW69-DOUT)") (class "Default")
      (node (ref "SW69") (pin "4") (pinfunction "DOUT_4") (pintype "passive"))
      (node (ref "SW70") (pin "6") (pinfunction "DIN_6") (pintype "passive"))
    )
    (net (code "181") (name "Net-(SW70-DOUT)") (class "Default")
      (node (ref "SW70") (pin "4") (pinfunction "DOUT_4") (pintype "passive"))
      (node (ref "SW71") (pin "6") (pinfunction "DIN_6") (pintype "passive"))
    )
    (net (code "182") (name "Net-(SW71-DOUT)") (class "Default")
      (node (ref "SW71") (pin "4") (pinfunction "DOUT_4") (pintype "passive"))
      (node (ref "SW72") (pin "6") (pinfunction "DIN_6") (pintype "passive"))
    )
    (net (code "183") (name "Net-(SW72-DOUT)") (class "Default")
      (node (ref "SW72") (pin "4") (pinfunction "DOUT_4") (pintype "passive"))
      (node (ref "SW73") (pin "6") (pinfunction "DIN_6") (pintype "passive"))
    )
    (net (code "184") (name "Net-(SW73-DOUT)") (class "Default")
      (node (ref "SW73") (pin "4") (pinfunction "DOUT_4") (pintype "passive"))
      (node (ref "SW74") (pin "6") (pinfunction "DIN_6") (pintype "passive"))
    )
    (net (code "185") (name "Net-(SW75-DOUT)") (class "Default")
      (node (ref "SW75") (pin "4") (pinfunction "DOUT_4") (pintype "passive"))
      (node (ref "SW76") (pin "6") (pinfunction "DIN_6") (pintype "passive"))
    )
    (net (code "186") (name "Net-(SW76-DOUT)") (class "Default")
      (node (ref "SW76") (pin "4") (pinfunction "DOUT_4") (pintype "passive"))
      (node (ref "SW77") (pin "6") (pinfunction "DIN_6") (pintype "passive"))
    )
    (net (code "187") (name "Net-(SW77-DOUT)") (class "Default")
      (node (ref "SW77") (pin "4") (pinfunction "DOUT_4") (pintype "passive"))
      (node (ref "SW78") (pin "6") (pinfunction "DIN_6") (pintype "passive"))
    )
    (net (code "188") (name "Net-(SW78-DOUT)") (class "Default")
      (node (ref "SW78") (pin "4") (pinfunction "DOUT_4") (pintype "passive"))
      (node (ref "SW79") (pin "6") (pinfunction "DIN_6") (pintype "passive"))
    )
    (net (code "189") (name "Net-(SW79-DOUT)") (class "Default")
      (node (ref "SW79") (pin "4") (pinfunction "DOUT_4") (pintype "passive"))
      (node (ref "SW80") (pin "6") (pinfunction "DIN_6") (pintype "passive"))
    )
    (net (code "190") (name "Net-(SW80-DOUT)") (class "Default")
      (node (ref "SW80") (pin "4") (pinfunction "DOUT_4") (pintype "passive"))
      (node (ref "SW81") (pin "6") (pinfunction "DIN_6") (pintype "passive"))
    )
    (net (code "191") (name "Net-(SW81-DOUT)") (class "Default")
      (node (ref "SW81") (pin "4") (pinfunction "DOUT_4") (pintype "passive"))
      (node (ref "SW82") (pin "6") (pinfunction "DIN_6") (pintype "passive"))
    )
    (net (code "192") (name "Net-(SW82-DOUT)") (class "Default")
      (node (ref "SW82") (pin "4") (pinfunction "DOUT_4") (pintype "passive"))
      (node (ref "SW83") (pin "6") (pinfunction "DIN_6") (pintype "passive"))
    )
    (net (code "193") (name "Net-(SW83-DOUT)") (class "Default")
      (node (ref "SW83") (pin "4") (pinfunction "DOUT_4") (pintype "passive"))
      (node (ref "SW84") (pin "6") (pinfunction "DIN_6") (pintype "passive"))
    )
    (net (code "194") (name "Net-(SW84-DOUT)") (class "Default")
      (node (ref "SW84") (pin "4") (pinfunction "DOUT_4") (pintype "passive"))
      (node (ref "SW85") (pin "6") (pinfunction "DIN_6") (pintype "passive"))
    )
    (net (code "195") (name "Net-(SW85-DOUT)") (class "Default")
      (node (ref "SW85") (pin "4") (pinfunction "DOUT_4") (pintype "passive"))
      (node (ref "SW86") (pin "6") (pinfunction "DIN_6") (pintype "passive"))
    )
    (net (code "196") (name "Net-(SW86-DOUT)") (class "Default")
      (node (ref "SW86") (pin "4") (pinfunction "DOUT_4") (pintype "passive"))
      (node (ref "SW87") (pin "6") (pinfunction "DIN_6") (pintype "passive"))
    )
    (net (code "197") (name "VCC5V") (class "Default")
      (node (ref "SW1") (pin "3") (pinfunction "VDD_3") (pintype "passive"))
      (node (ref "SW10") (pin "3") (pinfunction "VDD_3") (pintype "passive"))
      (node (ref "SW11") (pin "3") (pinfunction "VDD_3") (pintype "passive"))
      (node (ref "SW12") (pin "3") (pinfunction "VDD_3") (pintype "passive"))
      (node (ref "SW13") (pin "3") (pinfunction "VDD_3") (pintype "passive"))
      (node (ref "SW14") (pin "3") (pinfunction "VDD_3") (pintype "passive"))
      (node (ref "SW15") (pin "3") (pinfunction "VDD_3") (pintype "passive"))
      (node (ref "SW16") (pin "3") (pinfunction "VDD_3") (pintype "passive"))
      (node (ref "SW17") (pin "3") (pinfunction "VDD_3") (pintype "passive"))
      (node (ref "SW18") (pin "3") (pinfunction "VDD_3") (pintype "passive"))
      (node (ref "SW19") (pin "3") (pinfunction "VDD_3") (pintype "passive"))
      (node (ref "SW2") (pin "3") (pinfunction "VDD_3") (pintype "passive"))
      (node (ref "SW20") (pin "3") (pinfunction "VDD_3") (pintype "passive"))
      (node (ref "SW21") (pin "3") (pinfunction "VDD_3") (pintype "passive"))
      (node (ref "SW22") (pin "3") (pinfunction "VDD_3") (pintype "passive"))
      (node (ref "SW23") (pin "3") (pinfunction "VDD_3") (pintype "passive"))
      (node (ref "SW24") (pin "3") (pinfunction "VDD_3") (pintype "passive"))
      (node (ref "SW25") (pin "3") (pinfunction "VDD_3") (pintype "passive"))
      (node (ref "SW26") (pin "3") (pinfunction "VDD_3") (pintype "passive"))
      (node (ref "SW27") (pin "3") (pinfunction "VDD_3") (pintype "passive"))
      (node (ref "SW28") (pin "3") (pinfunction "VDD_3") (pintype "passive"))
      (node (ref "SW29") (pin "3") (pinfunction "VDD_3") (pintype "passive"))
      (node (ref "SW3") (pin "3") (pinfunction "VDD_3") (pintype "passive"))
      (node (ref "SW30") (pin "3") (pinfunction "VDD_3") (pintype "passive"))
      (node (ref "SW31") (pin "3") (pinfunction "VDD_3") (pintype "passive"))
      (node (ref "SW32") (pin "3") (pinfunction "VDD_3") (pintype "passive"))
      (node (ref "SW33") (pin "3") (pinfunction "VDD_3") (pintype "passive"))
      (node (ref "SW34") (pin "3") (pinfunction "VDD_3") (pintype "passive"))
      (node (ref "SW35") (pin "3") (pinfunction "VDD_3") (pintype "passive"))
      (node (ref "SW36") (pin "3") (pinfunction "VDD_3") (pintype "passive"))
      (node (ref "SW37") (pin "3") (pinfunction "VDD_3") (pintype "passive"))
      (node (ref "SW38") (pin "3") (pinfunction "VDD_3") (pintype "passive"))
      (node (ref "SW39") (pin "3") (pinfunction "VDD_3") (pintype "passive"))
      (node (ref "SW4") (pin "3") (pinfunction "VDD_3") (pintype "passive"))
      (node (ref "SW40") (pin "3") (pinfunction "VDD_3") (pintype "passive"))
      (node (ref "SW41") (pin "3") (pinfunction "VDD_3") (pintype "passive"))
      (node (ref "SW42") (pin "3") (pinfunction "VDD_3") (pintype "passive"))
      (node (ref "SW43") (pin "3") (pinfunction "VDD_3") (pintype "passive"))
      (node (ref "SW44") (pin "3") (pinfunction "VDD_3") (pintype "passive"))
      (node (ref "SW45") (pin "3") (pinfunction "VDD_3") (pintype "passive"))
      (node (ref "SW46") (pin "3") (pinfunction "VDD_3") (pintype "passive"))
      (node (ref "SW47") (pin "3") (pinfunction "VDD_3") (pintype "passive"))
      (node (ref "SW48") (pin "3") (pinfunction "VDD_3") (pintype "passive"))
      (node (ref "SW49") (pin "3") (pinfunction "VDD_3") (pintype "passive"))
      (node (ref "SW5") (pin "3") (pinfunction "VDD_3") (pintype "passive"))
      (node (ref "SW50") (pin "3") (pinfunction "VDD_3") (pintype "passive"))
      (node (ref "SW51") (pin "3") (pinfunction "VDD_3") (pintype "passive"))
      (node (ref "SW52") (pin "3") (pinfunction "VDD_3") (pintype "passive"))
      (node (ref "SW53") (pin "3") (pinfunction "VDD_3") (pintype "passive"))
      (node (ref "SW54") (pin "3") (pinfunction "VDD_3") (pintype "passive"))
      (node (ref "SW55") (pin "3") (pinfunction "VDD_3") (pintype "passive"))
      (node (ref "SW56") (pin "3") (pinfunction "VDD_3") (pintype "passive"))
      (node (ref "SW57") (pin "3") (pinfunction "VDD_3") (pintype "passive"))
      (node (ref "SW58") (pin "3") (pinfunction "VDD_3") (pintype "passive"))
      (node (ref "SW59") (pin "3") (pinfunction "VDD_3") (pintype "passive"))
      (node (ref "SW6") (pin "3") (pinfunction "VDD_3") (pintype "passive"))
      (node (ref "SW60") (pin "3") (pinfunction "VDD_3") (pintype "passive"))
      (node (ref "SW61") (pin "3") (pinfunction "VDD_3") (pintype "passive"))
      (node (ref "SW62") (pin "3") (pinfunction "VDD_3") (pintype "passive"))
      (node (ref "SW63") (pin "3") (pinfunction "VDD_3") (pintype "passive"))
      (node (ref "SW64") (pin "3") (pinfunction "VDD_3") (pintype "passive"))
      (node (ref "SW65") (pin "3") (pinfunction "VDD_3") (pintype "passive"))
      (node (ref "SW66") (pin "3") (pinfunction "VDD_3") (pintype "passive"))
      (node (ref "SW67") (pin "3") (pinfunction "VDD_3") (pintype "passive"))
      (node (ref "SW68") (pin "3") (pinfunction "VDD_3") (pintype "passive"))
      (node (ref "SW69") (pin "3") (pinfunction "VDD_3") (pintype "passive"))
      (node (ref "SW7") (pin "3") (pinfunction "VDD_3") (pintype "passive"))
      (node (ref "SW70") (pin "3") (pinfunction "VDD_3") (pintype "passive"))
      (node (ref "SW71") (pin "3") (pinfunction "VDD_3") (pintype "passive"))
      (node (ref "SW72") (pin "3") (pinfunction "VDD_3") (pintype "passive"))
      (node (ref "SW73") (pin "3") (pinfunction "VDD_3") (pintype "passive"))
      (node (ref "SW74") (pin "3") (pinfunction "VDD_3") (pintype "passive"))
      (node (ref "SW75") (pin "3") (pinfunction "VDD_3") (pintype "passive"))
      (node (ref "SW76") (pin "3") (pinfunction "VDD_3") (pintype "passive"))
      (node (ref "SW77") (pin "3") (pinfunction "VDD_3") (pintype "passive"))
      (node (ref "SW78") (pin "3") (pinfunction "VDD_3") (pintype "passive"))
      (node (ref "SW79") (pin "3") (pinfunction "VDD_3") (pintype "passive"))
      (node (ref "SW8") (pin "3") (pinfunction "VDD_3") (pintype "passive"))
      (node (ref "SW80") (pin "3") (pinfunction "VDD_3") (pintype "passive"))
      (node (ref "SW81") (pin "3") (pinfunction "VDD_3") (pintype "passive"))
      (node (ref "SW82") (pin "3") (pinfunction "VDD_3") (pintype "passive"))
      (node (ref "SW83") (pin "3") (pinfunction "VDD_3") (pintype "passive"))
      (node (ref "SW84") (pin "3") (pinfunction "VDD_3") (pintype "passive"))
      (node (ref "SW85") (pin "3") (pinfunction "VDD_3") (pintype "passive"))
      (node (ref "SW86") (pin "3") (pinfunction "VDD_3") (pintype "passive"))
      (node (ref "SW87") (pin "3") (pinfunction "VDD_3") (pintype "passive"))
      (node (ref "SW9") (pin "3") (pinfunction "VDD_3") (pintype "passive"))
    )
    (net (code "198") (name "unconnected-(SW27-DOUT-Pad4)") (class "Default")
      (node (ref "SW27") (pin "4") (pinfunction "DOUT_4") (pintype "passive+no_connect"))
    )
    (net (code "199") (name "unconnected-(SW54-DOUT-Pad4)") (class "Default")
      (node (ref "SW54") (pin "4") (pinfunction "DOUT_4") (pintype "passive+no_connect"))
    )
    (net (code "200") (name "unconnected-(SW87-DOUT-Pad4)") (class "Default")
      (node (ref "SW87") (pin "4") (pinfunction "DOUT_4") (pintype "passive+no_connect"))
    )
  )
)
